# GS_02_Core.net
KiCad netlist of a schematic drawn in Altium Designer
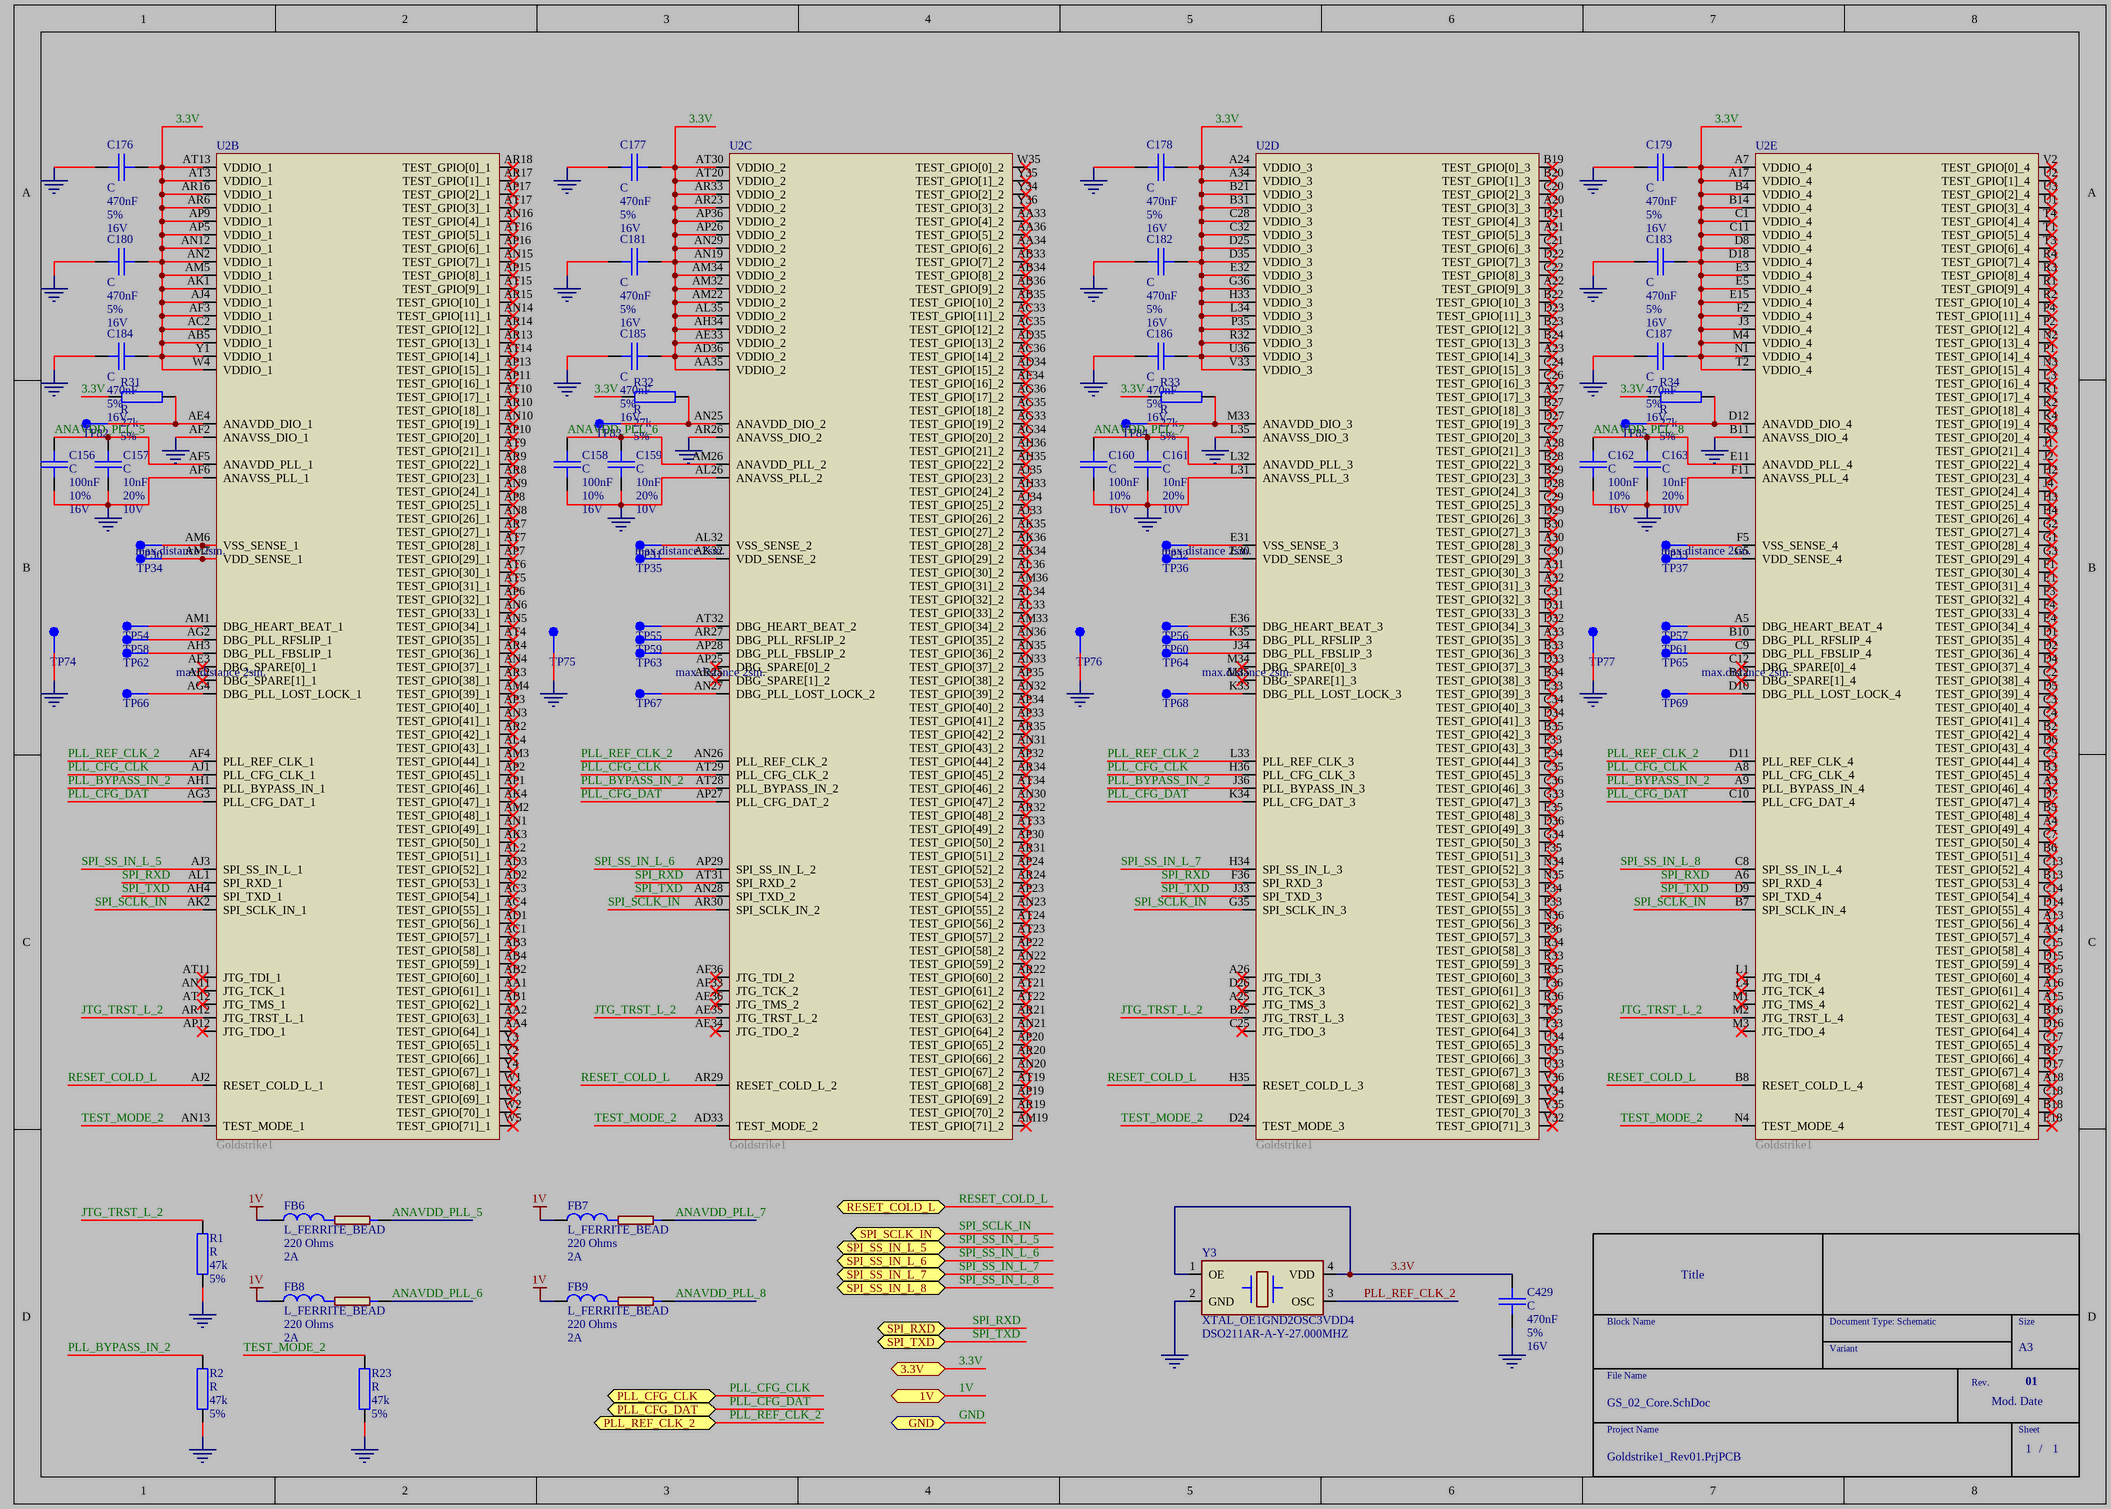
[diagram p0: GS_02_Core.SchDoc]

(export (version "E")
  (design (tool "Eeschema 10.0.6"))
  (components
    (comp (ref "C156")
      (value "C")
      (footprint "SMD_0603_CAPC1608X95N")
      (fields
        (field (name "DB_PART_NUMBER") "CAP000047357")
        (field (name "DB_VALUE") "100nF")
        (field (name "DB_TOLERANCE") "10%")
        (field (name "DB_VOLTAGE") "16V")
        (field (name "DB_MANUFACTURER_PART") "YAGEO      223878615649")
        (field (name "DB_APPROVED_BY") "VSN")
      )
      (libsource (lib "Database_Libs1") (part "C"))
    )
    (comp (ref "C157")
      (value "C")
      (footprint "SMD_0603_CAPC1608X95N")
      (fields
        (field (name "DB_PART_NUMBER") "CAP000038821")
        (field (name "DB_VALUE") "10nF")
        (field (name "DB_TOLERANCE") "20%")
        (field (name "DB_VOLTAGE") "10V")
        (field (name "DB_MANUFACTURER_PART") "KEMET    C0603C103M8GAC")
      )
      (libsource (lib "Database_Libs1") (part "C"))
    )
    (comp (ref "C158")
      (value "C")
      (footprint "SMD_0603_CAPC1608X95N")
      (fields
        (field (name "DB_PART_NUMBER") "CAP000047357")
        (field (name "DB_VALUE") "100nF")
        (field (name "DB_TOLERANCE") "10%")
        (field (name "DB_VOLTAGE") "16V")
        (field (name "DB_MANUFACTURER_PART") "YAGEO      223878615649")
        (field (name "DB_APPROVED_BY") "VSN")
      )
      (libsource (lib "Database_Libs1") (part "C"))
    )
    (comp (ref "C159")
      (value "C")
      (footprint "SMD_0603_CAPC1608X95N")
      (fields
        (field (name "DB_PART_NUMBER") "CAP000038821")
        (field (name "DB_VALUE") "10nF")
        (field (name "DB_TOLERANCE") "20%")
        (field (name "DB_VOLTAGE") "10V")
        (field (name "DB_MANUFACTURER_PART") "KEMET    C0603C103M8GAC")
      )
      (libsource (lib "Database_Libs1") (part "C"))
    )
    (comp (ref "C160")
      (value "C")
      (footprint "SMD_0603_CAPC1608X95N")
      (fields
        (field (name "DB_PART_NUMBER") "CAP000047357")
        (field (name "DB_VALUE") "100nF")
        (field (name "DB_TOLERANCE") "10%")
        (field (name "DB_VOLTAGE") "16V")
        (field (name "DB_MANUFACTURER_PART") "YAGEO      223878615649")
        (field (name "DB_APPROVED_BY") "VSN")
      )
      (libsource (lib "Database_Libs1") (part "C"))
    )
    (comp (ref "C161")
      (value "C")
      (footprint "SMD_0603_CAPC1608X95N")
      (fields
        (field (name "DB_PART_NUMBER") "CAP000038821")
        (field (name "DB_VALUE") "10nF")
        (field (name "DB_TOLERANCE") "20%")
        (field (name "DB_VOLTAGE") "10V")
        (field (name "DB_MANUFACTURER_PART") "KEMET    C0603C103M8GAC")
      )
      (libsource (lib "Database_Libs1") (part "C"))
    )
    (comp (ref "C162")
      (value "C")
      (footprint "SMD_0603_CAPC1608X95N")
      (fields
        (field (name "DB_PART_NUMBER") "CAP000047357")
        (field (name "DB_VALUE") "100nF")
        (field (name "DB_TOLERANCE") "10%")
        (field (name "DB_VOLTAGE") "16V")
        (field (name "DB_MANUFACTURER_PART") "YAGEO      223878615649")
        (field (name "DB_APPROVED_BY") "VSN")
      )
      (libsource (lib "Database_Libs1") (part "C"))
    )
    (comp (ref "C163")
      (value "C")
      (footprint "SMD_0603_CAPC1608X95N")
      (fields
        (field (name "DB_PART_NUMBER") "CAP000038821")
        (field (name "DB_VALUE") "10nF")
        (field (name "DB_TOLERANCE") "20%")
        (field (name "DB_VOLTAGE") "10V")
        (field (name "DB_MANUFACTURER_PART") "KEMET    C0603C103M8GAC")
      )
      (libsource (lib "Database_Libs1") (part "C"))
    )
    (comp (ref "C176")
      (value "C")
      (footprint "SMD_0603_CAPC1608X95N")
      (fields
        (field (name "DB_PART_NUMBER") "CAP000028169")
        (field (name "DB_VALUE") "470nF")
        (field (name "DB_TOLERANCE") "5%")
        (field (name "DB_VOLTAGE") "16V")
        (field (name "DB_MANUFACTURER_PART") "KEMET    C0603C474J4RAC")
      )
      (libsource (lib "Database_Libs1") (part "C"))
    )
    (comp (ref "C177")
      (value "C")
      (footprint "SMD_0603_CAPC1608X95N")
      (fields
        (field (name "DB_PART_NUMBER") "CAP000028169")
        (field (name "DB_VALUE") "470nF")
        (field (name "DB_TOLERANCE") "5%")
        (field (name "DB_VOLTAGE") "16V")
        (field (name "DB_MANUFACTURER_PART") "KEMET    C0603C474J4RAC")
      )
      (libsource (lib "Database_Libs1") (part "C"))
    )
    (comp (ref "C178")
      (value "C")
      (footprint "SMD_0603_CAPC1608X95N")
      (fields
        (field (name "DB_PART_NUMBER") "CAP000028169")
        (field (name "DB_VALUE") "470nF")
        (field (name "DB_TOLERANCE") "5%")
        (field (name "DB_VOLTAGE") "16V")
        (field (name "DB_MANUFACTURER_PART") "KEMET    C0603C474J4RAC")
      )
      (libsource (lib "Database_Libs1") (part "C"))
    )
    (comp (ref "C179")
      (value "C")
      (footprint "SMD_0603_CAPC1608X95N")
      (fields
        (field (name "DB_PART_NUMBER") "CAP000028169")
        (field (name "DB_VALUE") "470nF")
        (field (name "DB_TOLERANCE") "5%")
        (field (name "DB_VOLTAGE") "16V")
        (field (name "DB_MANUFACTURER_PART") "KEMET    C0603C474J4RAC")
      )
      (libsource (lib "Database_Libs1") (part "C"))
    )
    (comp (ref "C180")
      (value "C")
      (footprint "SMD_0603_CAPC1608X95N")
      (fields
        (field (name "DB_PART_NUMBER") "CAP000028169")
        (field (name "DB_VALUE") "470nF")
        (field (name "DB_TOLERANCE") "5%")
        (field (name "DB_VOLTAGE") "16V")
        (field (name "DB_MANUFACTURER_PART") "KEMET    C0603C474J4RAC")
      )
      (libsource (lib "Database_Libs1") (part "C"))
    )
    (comp (ref "C181")
      (value "C")
      (footprint "SMD_0603_CAPC1608X95N")
      (fields
        (field (name "DB_PART_NUMBER") "CAP000028169")
        (field (name "DB_VALUE") "470nF")
        (field (name "DB_TOLERANCE") "5%")
        (field (name "DB_VOLTAGE") "16V")
        (field (name "DB_MANUFACTURER_PART") "KEMET    C0603C474J4RAC")
      )
      (libsource (lib "Database_Libs1") (part "C"))
    )
    (comp (ref "C182")
      (value "C")
      (footprint "SMD_0603_CAPC1608X95N")
      (fields
        (field (name "DB_PART_NUMBER") "CAP000028169")
        (field (name "DB_VALUE") "470nF")
        (field (name "DB_TOLERANCE") "5%")
        (field (name "DB_VOLTAGE") "16V")
        (field (name "DB_MANUFACTURER_PART") "KEMET    C0603C474J4RAC")
      )
      (libsource (lib "Database_Libs1") (part "C"))
    )
    (comp (ref "C183")
      (value "C")
      (footprint "SMD_0603_CAPC1608X95N")
      (fields
        (field (name "DB_PART_NUMBER") "CAP000028169")
        (field (name "DB_VALUE") "470nF")
        (field (name "DB_TOLERANCE") "5%")
        (field (name "DB_VOLTAGE") "16V")
        (field (name "DB_MANUFACTURER_PART") "KEMET    C0603C474J4RAC")
      )
      (libsource (lib "Database_Libs1") (part "C"))
    )
    (comp (ref "C184")
      (value "C")
      (footprint "SMD_0603_CAPC1608X95N")
      (fields
        (field (name "DB_PART_NUMBER") "CAP000028169")
        (field (name "DB_VALUE") "470nF")
        (field (name "DB_TOLERANCE") "5%")
        (field (name "DB_VOLTAGE") "16V")
        (field (name "DB_MANUFACTURER_PART") "KEMET    C0603C474J4RAC")
      )
      (libsource (lib "Database_Libs1") (part "C"))
    )
    (comp (ref "C185")
      (value "C")
      (footprint "SMD_0603_CAPC1608X95N")
      (fields
        (field (name "DB_PART_NUMBER") "CAP000028169")
        (field (name "DB_VALUE") "470nF")
        (field (name "DB_TOLERANCE") "5%")
        (field (name "DB_VOLTAGE") "16V")
        (field (name "DB_MANUFACTURER_PART") "KEMET    C0603C474J4RAC")
      )
      (libsource (lib "Database_Libs1") (part "C"))
    )
    (comp (ref "C186")
      (value "C")
      (footprint "SMD_0603_CAPC1608X95N")
      (fields
        (field (name "DB_PART_NUMBER") "CAP000028169")
        (field (name "DB_VALUE") "470nF")
        (field (name "DB_TOLERANCE") "5%")
        (field (name "DB_VOLTAGE") "16V")
        (field (name "DB_MANUFACTURER_PART") "KEMET    C0603C474J4RAC")
      )
      (libsource (lib "Database_Libs1") (part "C"))
    )
    (comp (ref "C187")
      (value "C")
      (footprint "SMD_0603_CAPC1608X95N")
      (fields
        (field (name "DB_PART_NUMBER") "CAP000028169")
        (field (name "DB_VALUE") "470nF")
        (field (name "DB_TOLERANCE") "5%")
        (field (name "DB_VOLTAGE") "16V")
        (field (name "DB_MANUFACTURER_PART") "KEMET    C0603C474J4RAC")
      )
      (libsource (lib "Database_Libs1") (part "C"))
    )
    (comp (ref "C429")
      (value "C")
      (footprint "SMD_0603_CAPC1608X95N")
      (fields
        (field (name "DB_PART_NUMBER") "CAP000028169")
        (field (name "DB_VALUE") "470nF")
        (field (name "DB_TOLERANCE") "5%")
        (field (name "DB_VOLTAGE") "16V")
        (field (name "DB_MANUFACTURER_PART") "KEMET    C0603C474J4RAC")
      )
      (libsource (lib "Database_Libs1") (part "C"))
    )
    (comp (ref "FB6")
      (value "L_FERRITE_BEAD")
      (footprint "SMD_0805_INDC2012X105N")
      (fields
        (field (name "DB_PART_NUMBER") "IND000000029")
        (field (name "DB_VALUE") "220 Ohms")
        (field (name "DB_CURRENT") "2A")
        (field (name "DB_MANUFACTURER_PART") "MURATA       BLM21PG221SN1D")
        (field (name "DB_APPROVED_BY") "VSN")
      )
      (libsource (lib "Database_Libs1") (part "L_FERRITE_BEAD"))
    )
    (comp (ref "FB7")
      (value "L_FERRITE_BEAD")
      (footprint "SMD_0805_INDC2012X105N")
      (fields
        (field (name "DB_PART_NUMBER") "IND000000029")
        (field (name "DB_VALUE") "220 Ohms")
        (field (name "DB_CURRENT") "2A")
        (field (name "DB_MANUFACTURER_PART") "MURATA       BLM21PG221SN1D")
        (field (name "DB_APPROVED_BY") "VSN")
      )
      (libsource (lib "Database_Libs1") (part "L_FERRITE_BEAD"))
    )
    (comp (ref "FB8")
      (value "L_FERRITE_BEAD")
      (footprint "SMD_0805_INDC2012X105N")
      (fields
        (field (name "DB_PART_NUMBER") "IND000000029")
        (field (name "DB_VALUE") "220 Ohms")
        (field (name "DB_CURRENT") "2A")
        (field (name "DB_MANUFACTURER_PART") "MURATA       BLM21PG221SN1D")
        (field (name "DB_APPROVED_BY") "VSN")
      )
      (libsource (lib "Database_Libs1") (part "L_FERRITE_BEAD"))
    )
    (comp (ref "FB9")
      (value "L_FERRITE_BEAD")
      (footprint "SMD_0805_INDC2012X105N")
      (fields
        (field (name "DB_PART_NUMBER") "IND000000029")
        (field (name "DB_VALUE") "220 Ohms")
        (field (name "DB_CURRENT") "2A")
        (field (name "DB_MANUFACTURER_PART") "MURATA       BLM21PG221SN1D")
        (field (name "DB_APPROVED_BY") "VSN")
      )
      (libsource (lib "Database_Libs1") (part "L_FERRITE_BEAD"))
    )
    (comp (ref "R1")
      (value "R")
      (footprint "SMD_0603_RESC1608X55N")
      (fields
        (field (name "DB_PART_NUMBER") "RES000006462")
        (field (name "DB_VALUE") "47k")
        (field (name "DB_TOLERANCE") "5%")
        (field (name "DB_MANUFACTURER_PART") "YAGEO    RC0603JR-0747K")
      )
      (libsource (lib "Database_Libs1") (part "R"))
    )
    (comp (ref "R2")
      (value "R")
      (footprint "SMD_0603_RESC1608X55N")
      (fields
        (field (name "DB_PART_NUMBER") "RES000006462")
        (field (name "DB_VALUE") "47k")
        (field (name "DB_TOLERANCE") "5%")
        (field (name "DB_MANUFACTURER_PART") "YAGEO    RC0603JR-0747K")
      )
      (libsource (lib "Database_Libs1") (part "R"))
    )
    (comp (ref "R23")
      (value "R")
      (footprint "SMD_0603_RESC1608X55N")
      (fields
        (field (name "DB_PART_NUMBER") "RES000006462")
        (field (name "DB_VALUE") "47k")
        (field (name "DB_TOLERANCE") "5%")
        (field (name "DB_MANUFACTURER_PART") "YAGEO    RC0603JR-0747K")
      )
      (libsource (lib "Database_Libs1") (part "R"))
    )
    (comp (ref "R31")
      (value "R")
      (footprint "SMD_0603_RESC1608X55N")
      (fields
        (field (name "DB_PART_NUMBER") "RES000006456")
        (field (name "DB_VALUE") "27k")
        (field (name "DB_TOLERANCE") "5%")
        (field (name "DB_MANUFACTURER_PART") "YAGEO    RC0603JR-0727K")
      )
      (libsource (lib "Database_Libs1") (part "R"))
    )
    (comp (ref "R32")
      (value "R")
      (footprint "SMD_0603_RESC1608X55N")
      (fields
        (field (name "DB_PART_NUMBER") "RES000006456")
        (field (name "DB_VALUE") "27k")
        (field (name "DB_TOLERANCE") "5%")
        (field (name "DB_MANUFACTURER_PART") "YAGEO    RC0603JR-0727K")
      )
      (libsource (lib "Database_Libs1") (part "R"))
    )
    (comp (ref "R33")
      (value "R")
      (footprint "SMD_0603_RESC1608X55N")
      (fields
        (field (name "DB_PART_NUMBER") "RES000006456")
        (field (name "DB_VALUE") "27k")
        (field (name "DB_TOLERANCE") "5%")
        (field (name "DB_MANUFACTURER_PART") "YAGEO    RC0603JR-0727K")
      )
      (libsource (lib "Database_Libs1") (part "R"))
    )
    (comp (ref "R34")
      (value "R")
      (footprint "SMD_0603_RESC1608X55N")
      (fields
        (field (name "DB_PART_NUMBER") "RES000006456")
        (field (name "DB_VALUE") "27k")
        (field (name "DB_TOLERANCE") "5%")
        (field (name "DB_MANUFACTURER_PART") "YAGEO    RC0603JR-0727K")
      )
      (libsource (lib "Database_Libs1") (part "R"))
    )
    (comp (ref "TP30")
      (value "TEST_POINT_1")
      (footprint "SMD_TP_100-254")
      (fields (field (name "DB_PART_NUMBER") "TPO000000001"))
      (libsource (lib "Database_Libs1") (part "TEST_POINT_1"))
    )
    (comp (ref "TP31")
      (value "TEST_POINT_1")
      (footprint "SMD_TP_100-254")
      (fields (field (name "DB_PART_NUMBER") "TPO000000001"))
      (libsource (lib "Database_Libs1") (part "TEST_POINT_1"))
    )
    (comp (ref "TP32")
      (value "TEST_POINT_1")
      (footprint "SMD_TP_100-254")
      (fields (field (name "DB_PART_NUMBER") "TPO000000001"))
      (libsource (lib "Database_Libs1") (part "TEST_POINT_1"))
    )
    (comp (ref "TP33")
      (value "TEST_POINT_1")
      (footprint "SMD_TP_100-254")
      (fields (field (name "DB_PART_NUMBER") "TPO000000001"))
      (libsource (lib "Database_Libs1") (part "TEST_POINT_1"))
    )
    (comp (ref "TP34")
      (value "TEST_POINT_1")
      (footprint "SMD_TP_100-254")
      (fields (field (name "DB_PART_NUMBER") "TPO000000001"))
      (libsource (lib "Database_Libs1") (part "TEST_POINT_1"))
    )
    (comp (ref "TP35")
      (value "TEST_POINT_1")
      (footprint "SMD_TP_100-254")
      (fields (field (name "DB_PART_NUMBER") "TPO000000001"))
      (libsource (lib "Database_Libs1") (part "TEST_POINT_1"))
    )
    (comp (ref "TP36")
      (value "TEST_POINT_1")
      (footprint "SMD_TP_100-254")
      (fields (field (name "DB_PART_NUMBER") "TPO000000001"))
      (libsource (lib "Database_Libs1") (part "TEST_POINT_1"))
    )
    (comp (ref "TP37")
      (value "TEST_POINT_1")
      (footprint "SMD_TP_100-254")
      (fields (field (name "DB_PART_NUMBER") "TPO000000001"))
      (libsource (lib "Database_Libs1") (part "TEST_POINT_1"))
    )
    (comp (ref "TP54")
      (value "TEST_POINT_1")
      (footprint "SMD_TP_100-254")
      (fields (field (name "DB_PART_NUMBER") "TPO000000001"))
      (libsource (lib "Database_Libs1") (part "TEST_POINT_1"))
    )
    (comp (ref "TP55")
      (value "TEST_POINT_1")
      (footprint "SMD_TP_100-254")
      (fields (field (name "DB_PART_NUMBER") "TPO000000001"))
      (libsource (lib "Database_Libs1") (part "TEST_POINT_1"))
    )
    (comp (ref "TP56")
      (value "TEST_POINT_1")
      (footprint "SMD_TP_100-254")
      (fields (field (name "DB_PART_NUMBER") "TPO000000001"))
      (libsource (lib "Database_Libs1") (part "TEST_POINT_1"))
    )
    (comp (ref "TP57")
      (value "TEST_POINT_1")
      (footprint "SMD_TP_100-254")
      (fields (field (name "DB_PART_NUMBER") "TPO000000001"))
      (libsource (lib "Database_Libs1") (part "TEST_POINT_1"))
    )
    (comp (ref "TP58")
      (value "TEST_POINT_1")
      (footprint "SMD_TP_100-254")
      (fields (field (name "DB_PART_NUMBER") "TPO000000001"))
      (libsource (lib "Database_Libs1") (part "TEST_POINT_1"))
    )
    (comp (ref "TP59")
      (value "TEST_POINT_1")
      (footprint "SMD_TP_100-254")
      (fields (field (name "DB_PART_NUMBER") "TPO000000001"))
      (libsource (lib "Database_Libs1") (part "TEST_POINT_1"))
    )
    (comp (ref "TP60")
      (value "TEST_POINT_1")
      (footprint "SMD_TP_100-254")
      (fields (field (name "DB_PART_NUMBER") "TPO000000001"))
      (libsource (lib "Database_Libs1") (part "TEST_POINT_1"))
    )
    (comp (ref "TP61")
      (value "TEST_POINT_1")
      (footprint "SMD_TP_100-254")
      (fields (field (name "DB_PART_NUMBER") "TPO000000001"))
      (libsource (lib "Database_Libs1") (part "TEST_POINT_1"))
    )
    (comp (ref "TP62")
      (value "TEST_POINT_1")
      (footprint "SMD_TP_100-254")
      (fields (field (name "DB_PART_NUMBER") "TPO000000001"))
      (libsource (lib "Database_Libs1") (part "TEST_POINT_1"))
    )
    (comp (ref "TP63")
      (value "TEST_POINT_1")
      (footprint "SMD_TP_100-254")
      (fields (field (name "DB_PART_NUMBER") "TPO000000001"))
      (libsource (lib "Database_Libs1") (part "TEST_POINT_1"))
    )
    (comp (ref "TP64")
      (value "TEST_POINT_1")
      (footprint "SMD_TP_100-254")
      (fields (field (name "DB_PART_NUMBER") "TPO000000001"))
      (libsource (lib "Database_Libs1") (part "TEST_POINT_1"))
    )
    (comp (ref "TP65")
      (value "TEST_POINT_1")
      (footprint "SMD_TP_100-254")
      (fields (field (name "DB_PART_NUMBER") "TPO000000001"))
      (libsource (lib "Database_Libs1") (part "TEST_POINT_1"))
    )
    (comp (ref "TP66")
      (value "TEST_POINT_1")
      (footprint "SMD_TP_100-254")
      (fields (field (name "DB_PART_NUMBER") "TPO000000001"))
      (libsource (lib "Database_Libs1") (part "TEST_POINT_1"))
    )
    (comp (ref "TP67")
      (value "TEST_POINT_1")
      (footprint "SMD_TP_100-254")
      (fields (field (name "DB_PART_NUMBER") "TPO000000001"))
      (libsource (lib "Database_Libs1") (part "TEST_POINT_1"))
    )
    (comp (ref "TP68")
      (value "TEST_POINT_1")
      (footprint "SMD_TP_100-254")
      (fields (field (name "DB_PART_NUMBER") "TPO000000001"))
      (libsource (lib "Database_Libs1") (part "TEST_POINT_1"))
    )
    (comp (ref "TP69")
      (value "TEST_POINT_1")
      (footprint "SMD_TP_100-254")
      (fields (field (name "DB_PART_NUMBER") "TPO000000001"))
      (libsource (lib "Database_Libs1") (part "TEST_POINT_1"))
    )
    (comp (ref "TP74")
      (value "TEST_POINT_1")
      (footprint "SMD_TP_100-254")
      (fields (field (name "DB_PART_NUMBER") "TPO000000001"))
      (libsource (lib "Database_Libs1") (part "TEST_POINT_1"))
    )
    (comp (ref "TP75")
      (value "TEST_POINT_1")
      (footprint "SMD_TP_100-254")
      (fields (field (name "DB_PART_NUMBER") "TPO000000001"))
      (libsource (lib "Database_Libs1") (part "TEST_POINT_1"))
    )
    (comp (ref "TP76")
      (value "TEST_POINT_1")
      (footprint "SMD_TP_100-254")
      (fields (field (name "DB_PART_NUMBER") "TPO000000001"))
      (libsource (lib "Database_Libs1") (part "TEST_POINT_1"))
    )
    (comp (ref "TP77")
      (value "TEST_POINT_1")
      (footprint "SMD_TP_100-254")
      (fields (field (name "DB_PART_NUMBER") "TPO000000001"))
      (libsource (lib "Database_Libs1") (part "TEST_POINT_1"))
    )
    (comp (ref "TP82")
      (value "TEST_POINT_1")
      (footprint "SMD_TP_100-254")
      (fields (field (name "DB_PART_NUMBER") "TPO000000001"))
      (libsource (lib "Database_Libs1") (part "TEST_POINT_1"))
    )
    (comp (ref "TP83")
      (value "TEST_POINT_1")
      (footprint "SMD_TP_100-254")
      (fields (field (name "DB_PART_NUMBER") "TPO000000001"))
      (libsource (lib "Database_Libs1") (part "TEST_POINT_1"))
    )
    (comp (ref "TP84")
      (value "TEST_POINT_1")
      (footprint "SMD_TP_100-254")
      (fields (field (name "DB_PART_NUMBER") "TPO000000001"))
      (libsource (lib "Database_Libs1") (part "TEST_POINT_1"))
    )
    (comp (ref "TP85")
      (value "TEST_POINT_1")
      (footprint "SMD_TP_100-254")
      (fields (field (name "DB_PART_NUMBER") "TPO000000001"))
      (libsource (lib "Database_Libs1") (part "TEST_POINT_1"))
    )
    (comp (ref "U2")
      (value "Goldstrike1")
      (footprint "SMD_BGA1296C100P36X36")
      (libsource (lib "Schlib1") (part "Goldstrike1"))
    )
    (comp (ref "Y3")
      (value "XTAL_OE1GND2OSC3VDD4")
      (footprint "SMD_OSCCC160X200X80-4N")
      (fields
        (field (name "DB_PART_NUMBER") "OSC000000015")
        (field (name "DB_VALUE") "DSO211AR-A-Y-27.000MHZ")
        (field (name "DB_MANUFACTURER_PART") "KDS DAISHINKU      DSO211AR-A-Y-27.000MHZ")
        (field (name "DB_APPROVED_BY") "VSN")
      )
      (libsource (lib "Database_Libs1") (part "XTAL_OE1GND2OSC3VDD4"))
    )
  )
  (nets
    (net (code "1") (name "/3.3V") (class "Default")
      (node (ref "C176") (pin "2") (pinfunction "2_2") (pintype "passive"))
      (node (ref "C177") (pin "2") (pinfunction "2_2") (pintype "passive"))
      (node (ref "C178") (pin "2") (pinfunction "2_2") (pintype "passive"))
      (node (ref "C179") (pin "2") (pinfunction "2_2") (pintype "passive"))
      (node (ref "C180") (pin "2") (pinfunction "2_2") (pintype "passive"))
      (node (ref "C181") (pin "2") (pinfunction "2_2") (pintype "passive"))
      (node (ref "C182") (pin "2") (pinfunction "2_2") (pintype "passive"))
      (node (ref "C183") (pin "2") (pinfunction "2_2") (pintype "passive"))
      (node (ref "C184") (pin "2") (pinfunction "2_2") (pintype "passive"))
      (node (ref "C185") (pin "2") (pinfunction "2_2") (pintype "passive"))
      (node (ref "C186") (pin "2") (pinfunction "2_2") (pintype "passive"))
      (node (ref "C187") (pin "2") (pinfunction "2_2") (pintype "passive"))
      (node (ref "C429") (pin "2") (pinfunction "2_2") (pintype "passive"))
      (node (ref "R31") (pin "1") (pinfunction "1_1") (pintype "passive"))
      (node (ref "R32") (pin "1") (pinfunction "1_1") (pintype "passive"))
      (node (ref "R33") (pin "1") (pinfunction "1_1") (pintype "passive"))
      (node (ref "R34") (pin "1") (pinfunction "1_1") (pintype "passive"))
      (node (ref "U2") (pin "A17") (pinfunction "VDDIO_4_A17") (pintype "passive"))
      (node (ref "U2") (pin "A24") (pinfunction "VDDIO_3_A24") (pintype "passive"))
      (node (ref "U2") (pin "A34") (pinfunction "VDDIO_3_A34") (pintype "passive"))
      (node (ref "U2") (pin "A7") (pinfunction "VDDIO_4_A7") (pintype "passive"))
      (node (ref "U2") (pin "AA35") (pinfunction "VDDIO_2_AA35") (pintype "passive"))
      (node (ref "U2") (pin "AB5") (pinfunction "VDDIO_1_AB5") (pintype "passive"))
      (node (ref "U2") (pin "AC2") (pinfunction "VDDIO_1_AC2") (pintype "passive"))
      (node (ref "U2") (pin "AD36") (pinfunction "VDDIO_2_AD36") (pintype "passive"))
      (node (ref "U2") (pin "AE33") (pinfunction "VDDIO_2_AE33") (pintype "passive"))
      (node (ref "U2") (pin "AF3") (pinfunction "VDDIO_1_AF3") (pintype "passive"))
      (node (ref "U2") (pin "AH34") (pinfunction "VDDIO_2_AH34") (pintype "passive"))
      (node (ref "U2") (pin "AJ4") (pinfunction "VDDIO_1_AJ4") (pintype "passive"))
      (node (ref "U2") (pin "AK1") (pinfunction "VDDIO_1_AK1") (pintype "passive"))
      (node (ref "U2") (pin "AL35") (pinfunction "VDDIO_2_AL35") (pintype "passive"))
      (node (ref "U2") (pin "AM22") (pinfunction "VDDIO_2_AM22") (pintype "passive"))
      (node (ref "U2") (pin "AM32") (pinfunction "VDDIO_2_AM32") (pintype "passive"))
      (node (ref "U2") (pin "AM34") (pinfunction "VDDIO_2_AM34") (pintype "passive"))
      (node (ref "U2") (pin "AM5") (pinfunction "VDDIO_1_AM5") (pintype "passive"))
      (node (ref "U2") (pin "AN12") (pinfunction "VDDIO_1_AN12") (pintype "passive"))
      (node (ref "U2") (pin "AN19") (pinfunction "VDDIO_2_AN19") (pintype "passive"))
      (node (ref "U2") (pin "AN2") (pinfunction "VDDIO_1_AN2") (pintype "passive"))
      (node (ref "U2") (pin "AN29") (pinfunction "VDDIO_2_AN29") (pintype "passive"))
      (node (ref "U2") (pin "AP26") (pinfunction "VDDIO_2_AP26") (pintype "passive"))
      (node (ref "U2") (pin "AP36") (pinfunction "VDDIO_2_AP36") (pintype "passive"))
      (node (ref "U2") (pin "AP5") (pinfunction "VDDIO_1_AP5") (pintype "passive"))
      (node (ref "U2") (pin "AP9") (pinfunction "VDDIO_1_AP9") (pintype "passive"))
      (node (ref "U2") (pin "AR16") (pinfunction "VDDIO_1_AR16") (pintype "passive"))
      (node (ref "U2") (pin "AR23") (pinfunction "VDDIO_2_AR23") (pintype "passive"))
      (node (ref "U2") (pin "AR33") (pinfunction "VDDIO_2_AR33") (pintype "passive"))
      (node (ref "U2") (pin "AR6") (pinfunction "VDDIO_1_AR6") (pintype "passive"))
      (node (ref "U2") (pin "AT13") (pinfunction "VDDIO_1_AT13") (pintype "passive"))
      (node (ref "U2") (pin "AT20") (pinfunction "VDDIO_2_AT20") (pintype "passive"))
      (node (ref "U2") (pin "AT3") (pinfunction "VDDIO_1_AT3") (pintype "passive"))
      (node (ref "U2") (pin "AT30") (pinfunction "VDDIO_2_AT30") (pintype "passive"))
      (node (ref "U2") (pin "B14") (pinfunction "VDDIO_4_B14") (pintype "passive"))
      (node (ref "U2") (pin "B21") (pinfunction "VDDIO_3_B21") (pintype "passive"))
      (node (ref "U2") (pin "B31") (pinfunction "VDDIO_3_B31") (pintype "passive"))
      (node (ref "U2") (pin "B4") (pinfunction "VDDIO_4_B4") (pintype "passive"))
      (node (ref "U2") (pin "C1") (pinfunction "VDDIO_4_C1") (pintype "passive"))
      (node (ref "U2") (pin "C11") (pinfunction "VDDIO_4_C11") (pintype "passive"))
      (node (ref "U2") (pin "C28") (pinfunction "VDDIO_3_C28") (pintype "passive"))
      (node (ref "U2") (pin "C32") (pinfunction "VDDIO_3_C32") (pintype "passive"))
      (node (ref "U2") (pin "D18") (pinfunction "VDDIO_4_D18") (pintype "passive"))
      (node (ref "U2") (pin "D25") (pinfunction "VDDIO_3_D25") (pintype "passive"))
      (node (ref "U2") (pin "D35") (pinfunction "VDDIO_3_D35") (pintype "passive"))
      (node (ref "U2") (pin "D8") (pinfunction "VDDIO_4_D8") (pintype "passive"))
      (node (ref "U2") (pin "E15") (pinfunction "VDDIO_4_E15") (pintype "passive"))
      (node (ref "U2") (pin "E3") (pinfunction "VDDIO_4_E3") (pintype "passive"))
      (node (ref "U2") (pin "E32") (pinfunction "VDDIO_3_E32") (pintype "passive"))
      (node (ref "U2") (pin "E5") (pinfunction "VDDIO_4_E5") (pintype "passive"))
      (node (ref "U2") (pin "F2") (pinfunction "VDDIO_4_F2") (pintype "passive"))
      (node (ref "U2") (pin "G36") (pinfunction "VDDIO_3_G36") (pintype "passive"))
      (node (ref "U2") (pin "H33") (pinfunction "VDDIO_3_H33") (pintype "passive"))
      (node (ref "U2") (pin "J3") (pinfunction "VDDIO_4_J3") (pintype "passive"))
      (node (ref "U2") (pin "L34") (pinfunction "VDDIO_3_L34") (pintype "passive"))
      (node (ref "U2") (pin "M4") (pinfunction "VDDIO_4_M4") (pintype "passive"))
      (node (ref "U2") (pin "N1") (pinfunction "VDDIO_4_N1") (pintype "passive"))
      (node (ref "U2") (pin "P35") (pinfunction "VDDIO_3_P35") (pintype "passive"))
      (node (ref "U2") (pin "R32") (pinfunction "VDDIO_3_R32") (pintype "passive"))
      (node (ref "U2") (pin "T2") (pinfunction "VDDIO_4_T2") (pintype "passive"))
      (node (ref "U2") (pin "U36") (pinfunction "VDDIO_3_U36") (pintype "passive"))
      (node (ref "U2") (pin "V33") (pinfunction "VDDIO_3_V33") (pintype "passive"))
      (node (ref "U2") (pin "W4") (pinfunction "VDDIO_1_W4") (pintype "passive"))
      (node (ref "U2") (pin "Y1") (pinfunction "VDDIO_1_Y1") (pintype "passive"))
      (node (ref "Y3") (pin "1") (pinfunction "OE_1") (pintype "passive"))
      (node (ref "Y3") (pin "4") (pinfunction "VDD_4") (pintype "passive"))
    )
    (net (code "2") (name "/ANAVDD_PLL_5") (class "Default")
      (node (ref "C156") (pin "1") (pinfunction "1_1") (pintype "passive"))
      (node (ref "C157") (pin "1") (pinfunction "1_1") (pintype "passive"))
      (node (ref "FB6") (pin "2") (pinfunction "2_2") (pintype "passive"))
      (node (ref "U2") (pin "AF5") (pinfunction "ANAVDD_PLL_1_AF5") (pintype "passive"))
    )
    (net (code "3") (name "/ANAVDD_PLL_6") (class "Default")
      (node (ref "C158") (pin "1") (pinfunction "1_1") (pintype "passive"))
      (node (ref "C159") (pin "1") (pinfunction "1_1") (pintype "passive"))
      (node (ref "FB8") (pin "2") (pinfunction "2_2") (pintype "passive"))
      (node (ref "U2") (pin "AM26") (pinfunction "ANAVDD_PLL_2_AM26") (pintype "passive"))
    )
    (net (code "4") (name "/ANAVDD_PLL_7") (class "Default")
      (node (ref "C160") (pin "1") (pinfunction "1_1") (pintype "passive"))
      (node (ref "C161") (pin "1") (pinfunction "1_1") (pintype "passive"))
      (node (ref "FB7") (pin "2") (pinfunction "2_2") (pintype "passive"))
      (node (ref "U2") (pin "L32") (pinfunction "ANAVDD_PLL_3_L32") (pintype "passive"))
    )
    (net (code "5") (name "/ANAVDD_PLL_8") (class "Default")
      (node (ref "C162") (pin "1") (pinfunction "1_1") (pintype "passive"))
      (node (ref "C163") (pin "1") (pinfunction "1_1") (pintype "passive"))
      (node (ref "FB9") (pin "2") (pinfunction "2_2") (pintype "passive"))
      (node (ref "U2") (pin "E11") (pinfunction "ANAVDD_PLL_4_E11") (pintype "passive"))
    )
    (net (code "6") (name "/JTG_TRST_L_2") (class "Default")
      (node (ref "R1") (pin "1") (pinfunction "1_1") (pintype "passive"))
      (node (ref "U2") (pin "AE35") (pinfunction "JTG_TRST_L_2_AE35") (pintype "passive"))
      (node (ref "U2") (pin "AR12") (pinfunction "JTG_TRST_L_1_AR12") (pintype "passive"))
      (node (ref "U2") (pin "B25") (pinfunction "JTG_TRST_L_3_B25") (pintype "passive"))
      (node (ref "U2") (pin "M2") (pinfunction "JTG_TRST_L_4_M2") (pintype "passive"))
    )
    (net (code "7") (name "/PLL_BYPASS_IN_2") (class "Default")
      (node (ref "R2") (pin "1") (pinfunction "1_1") (pintype "passive"))
      (node (ref "U2") (pin "A9") (pinfunction "PLL_BYPASS_IN_4_A9") (pintype "passive"))
      (node (ref "U2") (pin "AH1") (pinfunction "PLL_BYPASS_IN_1_AH1") (pintype "passive"))
      (node (ref "U2") (pin "AT28") (pinfunction "PLL_BYPASS_IN_2_AT28") (pintype "passive"))
      (node (ref "U2") (pin "J36") (pinfunction "PLL_BYPASS_IN_3_J36") (pintype "passive"))
    )
    (net (code "8") (name "/PLL_CFG_CLK") (class "Default")
      (node (ref "U2") (pin "A8") (pinfunction "PLL_CFG_CLK_4_A8") (pintype "passive"))
      (node (ref "U2") (pin "AJ1") (pinfunction "PLL_CFG_CLK_1_AJ1") (pintype "passive"))
      (node (ref "U2") (pin "AT29") (pinfunction "PLL_CFG_CLK_2_AT29") (pintype "passive"))
      (node (ref "U2") (pin "H36") (pinfunction "PLL_CFG_CLK_3_H36") (pintype "passive"))
    )
    (net (code "9") (name "/PLL_CFG_DAT") (class "Default")
      (node (ref "U2") (pin "AG3") (pinfunction "PLL_CFG_DAT_1_AG3") (pintype "passive"))
      (node (ref "U2") (pin "AP27") (pinfunction "PLL_CFG_DAT_2_AP27") (pintype "passive"))
      (node (ref "U2") (pin "C10") (pinfunction "PLL_CFG_DAT_4_C10") (pintype "passive"))
      (node (ref "U2") (pin "K34") (pinfunction "PLL_CFG_DAT_3_K34") (pintype "passive"))
    )
    (net (code "10") (name "/PLL_REF_CLK_2") (class "Default")
      (node (ref "U2") (pin "AF4") (pinfunction "PLL_REF_CLK_1_AF4") (pintype "passive"))
      (node (ref "U2") (pin "AN26") (pinfunction "PLL_REF_CLK_2_AN26") (pintype "passive"))
      (node (ref "U2") (pin "D11") (pinfunction "PLL_REF_CLK_4_D11") (pintype "passive"))
      (node (ref "U2") (pin "L33") (pinfunction "PLL_REF_CLK_3_L33") (pintype "passive"))
      (node (ref "Y3") (pin "3") (pinfunction "OSC_3") (pintype "passive"))
    )
    (net (code "11") (name "/RESET_COLD_L") (class "Default")
      (node (ref "U2") (pin "AJ2") (pinfunction "RESET_COLD_L_1_AJ2") (pintype "passive"))
      (node (ref "U2") (pin "AR29") (pinfunction "RESET_COLD_L_2_AR29") (pintype "passive"))
      (node (ref "U2") (pin "B8") (pinfunction "RESET_COLD_L_4_B8") (pintype "passive"))
      (node (ref "U2") (pin "H35") (pinfunction "RESET_COLD_L_3_H35") (pintype "passive"))
    )
    (net (code "12") (name "/SPI_RXD") (class "Default")
      (node (ref "U2") (pin "A6") (pinfunction "SPI_RXD_4_A6") (pintype "passive"))
      (node (ref "U2") (pin "AL1") (pinfunction "SPI_RXD_1_AL1") (pintype "passive"))
      (node (ref "U2") (pin "AT31") (pinfunction "SPI_RXD_2_AT31") (pintype "passive"))
      (node (ref "U2") (pin "F36") (pinfunction "SPI_RXD_3_F36") (pintype "passive"))
    )
    (net (code "13") (name "/SPI_SCLK_IN") (class "Default")
      (node (ref "U2") (pin "AK2") (pinfunction "SPI_SCLK_IN_1_AK2") (pintype "passive"))
      (node (ref "U2") (pin "AR30") (pinfunction "SPI_SCLK_IN_2_AR30") (pintype "passive"))
      (node (ref "U2") (pin "B7") (pinfunction "SPI_SCLK_IN_4_B7") (pintype "passive"))
      (node (ref "U2") (pin "G35") (pinfunction "SPI_SCLK_IN_3_G35") (pintype "passive"))
    )
    (net (code "14") (name "/SPI_SS_IN_L_5") (class "Default")
      (node (ref "U2") (pin "AJ3") (pinfunction "SPI_SS_IN_L_1_AJ3") (pintype "passive"))
    )
    (net (code "15") (name "/SPI_SS_IN_L_6") (class "Default")
      (node (ref "U2") (pin "AP29") (pinfunction "SPI_SS_IN_L_2_AP29") (pintype "passive"))
    )
    (net (code "16") (name "/SPI_SS_IN_L_7") (class "Default")
      (node (ref "U2") (pin "H34") (pinfunction "SPI_SS_IN_L_3_H34") (pintype "passive"))
    )
    (net (code "17") (name "/SPI_SS_IN_L_8") (class "Default")
      (node (ref "U2") (pin "C8") (pinfunction "SPI_SS_IN_L_4_C8") (pintype "passive"))
    )
    (net (code "18") (name "/SPI_TXD") (class "Default")
      (node (ref "U2") (pin "AH4") (pinfunction "SPI_TXD_1_AH4") (pintype "passive"))
      (node (ref "U2") (pin "AN28") (pinfunction "SPI_TXD_2_AN28") (pintype "passive"))
      (node (ref "U2") (pin "D9") (pinfunction "SPI_TXD_4_D9") (pintype "passive"))
      (node (ref "U2") (pin "J33") (pinfunction "SPI_TXD_3_J33") (pintype "passive"))
    )
    (net (code "19") (name "/TEST_MODE_2") (class "Default")
      (node (ref "R23") (pin "1") (pinfunction "1_1") (pintype "passive"))
      (node (ref "U2") (pin "AD33") (pinfunction "TEST_MODE_2_AD33") (pintype "passive"))
      (node (ref "U2") (pin "AN13") (pinfunction "TEST_MODE_1_AN13") (pintype "passive"))
      (node (ref "U2") (pin "D24") (pinfunction "TEST_MODE_3_D24") (pintype "passive"))
      (node (ref "U2") (pin "N4") (pinfunction "TEST_MODE_4_N4") (pintype "passive"))
    )
    (net (code "20") (name "1V") (class "Default")
      (node (ref "FB6") (pin "1") (pinfunction "1_1") (pintype "passive"))
      (node (ref "FB7") (pin "1") (pinfunction "1_1") (pintype "passive"))
      (node (ref "FB8") (pin "1") (pinfunction "1_1") (pintype "passive"))
      (node (ref "FB9") (pin "1") (pinfunction "1_1") (pintype "passive"))
    )
    (net (code "21") (name "GND") (class "Default")
      (node (ref "C156") (pin "2") (pinfunction "2_2") (pintype "passive"))
      (node (ref "C157") (pin "2") (pinfunction "2_2") (pintype "passive"))
      (node (ref "C158") (pin "2") (pinfunction "2_2") (pintype "passive"))
      (node (ref "C159") (pin "2") (pinfunction "2_2") (pintype "passive"))
      (node (ref "C160") (pin "2") (pinfunction "2_2") (pintype "passive"))
      (node (ref "C161") (pin "2") (pinfunction "2_2") (pintype "passive"))
      (node (ref "C162") (pin "2") (pinfunction "2_2") (pintype "passive"))
      (node (ref "C163") (pin "2") (pinfunction "2_2") (pintype "passive"))
      (node (ref "C176") (pin "1") (pinfunction "1_1") (pintype "passive"))
      (node (ref "C177") (pin "1") (pinfunction "1_1") (pintype "passive"))
      (node (ref "C178") (pin "1") (pinfunction "1_1") (pintype "passive"))
      (node (ref "C179") (pin "1") (pinfunction "1_1") (pintype "passive"))
      (node (ref "C180") (pin "1") (pinfunction "1_1") (pintype "passive"))
      (node (ref "C181") (pin "1") (pinfunction "1_1") (pintype "passive"))
      (node (ref "C182") (pin "1") (pinfunction "1_1") (pintype "passive"))
      (node (ref "C183") (pin "1") (pinfunction "1_1") (pintype "passive"))
      (node (ref "C184") (pin "1") (pinfunction "1_1") (pintype "passive"))
      (node (ref "C185") (pin "1") (pinfunction "1_1") (pintype "passive"))
      (node (ref "C186") (pin "1") (pinfunction "1_1") (pintype "passive"))
      (node (ref "C187") (pin "1") (pinfunction "1_1") (pintype "passive"))
      (node (ref "C429") (pin "1") (pinfunction "1_1") (pintype "passive"))
      (node (ref "R1") (pin "2") (pinfunction "2_2") (pintype "passive"))
      (node (ref "R2") (pin "2") (pinfunction "2_2") (pintype "passive"))
      (node (ref "R23") (pin "2") (pinfunction "2_2") (pintype "passive"))
      (node (ref "TP74") (pin "1") (pinfunction "1_1") (pintype "passive"))
      (node (ref "TP75") (pin "1") (pinfunction "1_1") (pintype "passive"))
      (node (ref "TP76") (pin "1") (pinfunction "1_1") (pintype "passive"))
      (node (ref "TP77") (pin "1") (pinfunction "1_1") (pintype "passive"))
      (node (ref "U2") (pin "AF2") (pinfunction "ANAVSS_DIO_1_AF2") (pintype "passive"))
      (node (ref "U2") (pin "AF6") (pinfunction "ANAVSS_PLL_1_AF6") (pintype "passive"))
      (node (ref "U2") (pin "AL26") (pinfunction "ANAVSS_PLL_2_AL26") (pintype "passive"))
      (node (ref "U2") (pin "AR26") (pinfunction "ANAVSS_DIO_2_AR26") (pintype "passive"))
      (node (ref "U2") (pin "B11") (pinfunction "ANAVSS_DIO_4_B11") (pintype "passive"))
      (node (ref "U2") (pin "F11") (pinfunction "ANAVSS_PLL_4_F11") (pintype "passive"))
      (node (ref "U2") (pin "L31") (pinfunction "ANAVSS_PLL_3_L31") (pintype "passive"))
      (node (ref "U2") (pin "L35") (pinfunction "ANAVSS_DIO_3_L35") (pintype "passive"))
      (node (ref "Y3") (pin "2") (pinfunction "GND_2") (pintype "passive"))
    )
    (net (code "22") (name "Net-(U2B-ANAVDD_DIO_1)") (class "Default")
      (node (ref "R31") (pin "2") (pinfunction "2_2") (pintype "passive"))
      (node (ref "TP82") (pin "1") (pinfunction "1_1") (pintype "passive"))
      (node (ref "U2") (pin "AE4") (pinfunction "ANAVDD_DIO_1_AE4") (pintype "passive"))
    )
    (net (code "23") (name "Net-(U2B-DBG_HEART_BEAT_1)") (class "Default")
      (node (ref "TP54") (pin "1") (pinfunction "1_1") (pintype "passive"))
      (node (ref "U2") (pin "AM1") (pinfunction "DBG_HEART_BEAT_1_AM1") (pintype "passive"))
    )
    (net (code "24") (name "Net-(U2B-DBG_PLL_FBSLIP_1)") (class "Default")
      (node (ref "TP62") (pin "1") (pinfunction "1_1") (pintype "passive"))
      (node (ref "U2") (pin "AH3") (pinfunction "DBG_PLL_FBSLIP_1_AH3") (pintype "passive"))
    )
    (net (code "25") (name "Net-(U2B-DBG_PLL_LOST_LOCK_1)") (class "Default")
      (node (ref "TP66") (pin "1") (pinfunction "1_1") (pintype "passive"))
      (node (ref "U2") (pin "AG4") (pinfunction "DBG_PLL_LOST_LOCK_1_AG4") (pintype "passive"))
    )
    (net (code "26") (name "Net-(U2B-DBG_PLL_RFSLIP_1)") (class "Default")
      (node (ref "TP58") (pin "1") (pinfunction "1_1") (pintype "passive"))
      (node (ref "U2") (pin "AG2") (pinfunction "DBG_PLL_RFSLIP_1_AG2") (pintype "passive"))
    )
    (net (code "27") (name "Net-(U2B-VDD_SENSE_1)") (class "Default")
      (node (ref "TP34") (pin "1") (pinfunction "1_1") (pintype "passive"))
      (node (ref "U2") (pin "AM7") (pinfunction "VDD_SENSE_1_AM7") (pintype "passive"))
    )
    (net (code "28") (name "Net-(U2B-VSS_SENSE_1)") (class "Default")
      (node (ref "TP30") (pin "1") (pinfunction "1_1") (pintype "passive"))
      (node (ref "U2") (pin "AM6") (pinfunction "VSS_SENSE_1_AM6") (pintype "passive"))
    )
    (net (code "29") (name "Net-(U2C-ANAVDD_DIO_2)") (class "Default")
      (node (ref "R32") (pin "2") (pinfunction "2_2") (pintype "passive"))
      (node (ref "TP83") (pin "1") (pinfunction "1_1") (pintype "passive"))
      (node (ref "U2") (pin "AN25") (pinfunction "ANAVDD_DIO_2_AN25") (pintype "passive"))
    )
    (net (code "30") (name "Net-(U2C-DBG_HEART_BEAT_2)") (class "Default")
      (node (ref "TP55") (pin "1") (pinfunction "1_1") (pintype "passive"))
      (node (ref "U2") (pin "AT32") (pinfunction "DBG_HEART_BEAT_2_AT32") (pintype "passive"))
    )
    (net (code "31") (name "Net-(U2C-DBG_PLL_FBSLIP_2)") (class "Default")
      (node (ref "TP63") (pin "1") (pinfunction "1_1") (pintype "passive"))
      (node (ref "U2") (pin "AP28") (pinfunction "DBG_PLL_FBSLIP_2_AP28") (pintype "passive"))
    )
    (net (code "32") (name "Net-(U2C-DBG_PLL_LOST_LOCK_2)") (class "Default")
      (node (ref "TP67") (pin "1") (pinfunction "1_1") (pintype "passive"))
      (node (ref "U2") (pin "AN27") (pinfunction "DBG_PLL_LOST_LOCK_2_AN27") (pintype "passive"))
    )
    (net (code "33") (name "Net-(U2C-DBG_PLL_RFSLIP_2)") (class "Default")
      (node (ref "TP59") (pin "1") (pinfunction "1_1") (pintype "passive"))
      (node (ref "U2") (pin "AR27") (pinfunction "DBG_PLL_RFSLIP_2_AR27") (pintype "passive"))
    )
    (net (code "34") (name "Net-(U2C-VDD_SENSE_2)") (class "Default")
      (node (ref "TP35") (pin "1") (pinfunction "1_1") (pintype "passive"))
      (node (ref "U2") (pin "AK32") (pinfunction "VDD_SENSE_2_AK32") (pintype "passive"))
    )
    (net (code "35") (name "Net-(U2C-VSS_SENSE_2)") (class "Default")
      (node (ref "TP31") (pin "1") (pinfunction "1_1") (pintype "passive"))
      (node (ref "U2") (pin "AL32") (pinfunction "VSS_SENSE_2_AL32") (pintype "passive"))
    )
    (net (code "36") (name "Net-(U2D-ANAVDD_DIO_3)") (class "Default")
      (node (ref "R33") (pin "2") (pinfunction "2_2") (pintype "passive"))
      (node (ref "TP84") (pin "1") (pinfunction "1_1") (pintype "passive"))
      (node (ref "U2") (pin "M33") (pinfunction "ANAVDD_DIO_3_M33") (pintype "passive"))
    )
    (net (code "37") (name "Net-(U2D-DBG_HEART_BEAT_3)") (class "Default")
      (node (ref "TP56") (pin "1") (pinfunction "1_1") (pintype "passive"))
      (node (ref "U2") (pin "E36") (pinfunction "DBG_HEART_BEAT_3_E36") (pintype "passive"))
    )
    (net (code "38") (name "Net-(U2D-DBG_PLL_FBSLIP_3)") (class "Default")
      (node (ref "TP64") (pin "1") (pinfunction "1_1") (pintype "passive"))
      (node (ref "U2") (pin "J34") (pinfunction "DBG_PLL_FBSLIP_3_J34") (pintype "passive"))
    )
    (net (code "39") (name "Net-(U2D-DBG_PLL_LOST_LOCK_3)") (class "Default")
      (node (ref "TP68") (pin "1") (pinfunction "1_1") (pintype "passive"))
      (node (ref "U2") (pin "K33") (pinfunction "DBG_PLL_LOST_LOCK_3_K33") (pintype "passive"))
    )
    (net (code "40") (name "Net-(U2D-DBG_PLL_RFSLIP_3)") (class "Default")
      (node (ref "TP60") (pin "1") (pinfunction "1_1") (pintype "passive"))
      (node (ref "U2") (pin "K35") (pinfunction "DBG_PLL_RFSLIP_3_K35") (pintype "passive"))
    )
    (net (code "41") (name "Net-(U2D-VDD_SENSE_3)") (class "Default")
      (node (ref "TP36") (pin "1") (pinfunction "1_1") (pintype "passive"))
      (node (ref "U2") (pin "E30") (pinfunction "VDD_SENSE_3_E30") (pintype "passive"))
    )
    (net (code "42") (name "Net-(U2D-VSS_SENSE_3)") (class "Default")
      (node (ref "TP32") (pin "1") (pinfunction "1_1") (pintype "passive"))
      (node (ref "U2") (pin "E31") (pinfunction "VSS_SENSE_3_E31") (pintype "passive"))
    )
    (net (code "43") (name "Net-(U2E-ANAVDD_DIO_4)") (class "Default")
      (node (ref "R34") (pin "2") (pinfunction "2_2") (pintype "passive"))
      (node (ref "TP85") (pin "1") (pinfunction "1_1") (pintype "passive"))
      (node (ref "U2") (pin "D12") (pinfunction "ANAVDD_DIO_4_D12") (pintype "passive"))
    )
    (net (code "44") (name "Net-(U2E-DBG_HEART_BEAT_4)") (class "Default")
      (node (ref "TP57") (pin "1") (pinfunction "1_1") (pintype "passive"))
      (node (ref "U2") (pin "A5") (pinfunction "DBG_HEART_BEAT_4_A5") (pintype "passive"))
    )
    (net (code "45") (name "Net-(U2E-DBG_PLL_FBSLIP_4)") (class "Default")
      (node (ref "TP65") (pin "1") (pinfunction "1_1") (pintype "passive"))
      (node (ref "U2") (pin "C9") (pinfunction "DBG_PLL_FBSLIP_4_C9") (pintype "passive"))
    )
    (net (code "46") (name "Net-(U2E-DBG_PLL_LOST_LOCK_4)") (class "Default")
      (node (ref "TP69") (pin "1") (pinfunction "1_1") (pintype "passive"))
      (node (ref "U2") (pin "D10") (pinfunction "DBG_PLL_LOST_LOCK_4_D10") (pintype "passive"))
    )
    (net (code "47") (name "Net-(U2E-DBG_PLL_RFSLIP_4)") (class "Default")
      (node (ref "TP61") (pin "1") (pinfunction "1_1") (pintype "passive"))
      (node (ref "U2") (pin "B10") (pinfunction "DBG_PLL_RFSLIP_4_B10") (pintype "passive"))
    )
    (net (code "48") (name "Net-(U2E-VDD_SENSE_4)") (class "Default")
      (node (ref "TP37") (pin "1") (pinfunction "1_1") (pintype "passive"))
      (node (ref "U2") (pin "G5") (pinfunction "VDD_SENSE_4_G5") (pintype "passive"))
    )
    (net (code "49") (name "Net-(U2E-VSS_SENSE_4)") (class "Default")
      (node (ref "TP33") (pin "1") (pinfunction "1_1") (pintype "passive"))
      (node (ref "U2") (pin "F5") (pinfunction "VSS_SENSE_4_F5") (pintype "passive"))
    )
    (net (code "50") (name "unconnected-(U2B-DBG_SPARE[0]_1-PadAE3)") (class "Default")
      (node (ref "U2") (pin "AE3") (pinfunction "DBG_SPARE[0]_1_AE3") (pintype "passive+no_connect"))
    )
    (net (code "51") (name "unconnected-(U2B-DBG_SPARE[1]_1-PadAE2)") (class "Default")
      (node (ref "U2") (pin "AE2") (pinfunction "DBG_SPARE[1]_1_AE2") (pintype "passive+no_connect"))
    )
    (net (code "52") (name "unconnected-(U2B-JTG_TCK_1-PadAN11)") (class "Default")
      (node (ref "U2") (pin "AN11") (pinfunction "JTG_TCK_1_AN11") (pintype "passive+no_connect"))
    )
    (net (code "53") (name "unconnected-(U2B-JTG_TDI_1-PadAT11)") (class "Default")
      (node (ref "U2") (pin "AT11") (pinfunction "JTG_TDI_1_AT11") (pintype "passive+no_connect"))
    )
    (net (code "54") (name "unconnected-(U2B-JTG_TDO_1-PadAP12)") (class "Default")
      (node (ref "U2") (pin "AP12") (pinfunction "JTG_TDO_1_AP12") (pintype "passive+no_connect"))
    )
    (net (code "55") (name "unconnected-(U2B-JTG_TMS_1-PadAT12)") (class "Default")
      (node (ref "U2") (pin "AT12") (pinfunction "JTG_TMS_1_AT12") (pintype "passive+no_connect"))
    )
    (net (code "56") (name "unconnected-(U2B-TEST_GPIO[0]_1-PadAR18)") (class "Default")
      (node (ref "U2") (pin "AR18") (pinfunction "TEST_GPIO[0]_1_AR18") (pintype "passive+no_connect"))
    )
    (net (code "57") (name "unconnected-(U2B-TEST_GPIO[1]_1-PadAR17)") (class "Default")
      (node (ref "U2") (pin "AR17") (pinfunction "TEST_GPIO[1]_1_AR17") (pintype "passive+no_connect"))
    )
    (net (code "58") (name "unconnected-(U2B-TEST_GPIO[2]_1-PadAP17)") (class "Default")
      (node (ref "U2") (pin "AP17") (pinfunction "TEST_GPIO[2]_1_AP17") (pintype "passive+no_connect"))
    )
    (net (code "59") (name "unconnected-(U2B-TEST_GPIO[3]_1-PadAT17)") (class "Default")
      (node (ref "U2") (pin "AT17") (pinfunction "TEST_GPIO[3]_1_AT17") (pintype "passive+no_connect"))
    )
    (net (code "60") (name "unconnected-(U2B-TEST_GPIO[4]_1-PadAN16)") (class "Default")
      (node (ref "U2") (pin "AN16") (pinfunction "TEST_GPIO[4]_1_AN16") (pintype "passive+no_connect"))
    )
    (net (code "61") (name "unconnected-(U2B-TEST_GPIO[5]_1-PadAT16)") (class "Default")
      (node (ref "U2") (pin "AT16") (pinfunction "TEST_GPIO[5]_1_AT16") (pintype "passive+no_connect"))
    )
    (net (code "62") (name "unconnected-(U2B-TEST_GPIO[6]_1-PadAP16)") (class "Default")
      (node (ref "U2") (pin "AP16") (pinfunction "TEST_GPIO[6]_1_AP16") (pintype "passive+no_connect"))
    )
    (net (code "63") (name "unconnected-(U2B-TEST_GPIO[7]_1-PadAN15)") (class "Default")
      (node (ref "U2") (pin "AN15") (pinfunction "TEST_GPIO[7]_1_AN15") (pintype "passive+no_connect"))
    )
    (net (code "64") (name "unconnected-(U2B-TEST_GPIO[8]_1-PadAP15)") (class "Default")
      (node (ref "U2") (pin "AP15") (pinfunction "TEST_GPIO[8]_1_AP15") (pintype "passive+no_connect"))
    )
    (net (code "65") (name "unconnected-(U2B-TEST_GPIO[9]_1-PadAT15)") (class "Default")
      (node (ref "U2") (pin "AT15") (pinfunction "TEST_GPIO[9]_1_AT15") (pintype "passive+no_connect"))
    )
    (net (code "66") (name "unconnected-(U2B-TEST_GPIO[10]_1-PadAR15)") (class "Default")
      (node (ref "U2") (pin "AR15") (pinfunction "TEST_GPIO[10]_1_AR15") (pintype "passive+no_connect"))
    )
    (net (code "67") (name "unconnected-(U2B-TEST_GPIO[11]_1-PadAN14)") (class "Default")
      (node (ref "U2") (pin "AN14") (pinfunction "TEST_GPIO[11]_1_AN14") (pintype "passive+no_connect"))
    )
    (net (code "68") (name "unconnected-(U2B-TEST_GPIO[12]_1-PadAR14)") (class "Default")
      (node (ref "U2") (pin "AR14") (pinfunction "TEST_GPIO[12]_1_AR14") (pintype "passive+no_connect"))
    )
    (net (code "69") (name "unconnected-(U2B-TEST_GPIO[13]_1-PadAR13)") (class "Default")
      (node (ref "U2") (pin "AR13") (pinfunction "TEST_GPIO[13]_1_AR13") (pintype "passive+no_connect"))
    )
    (net (code "70") (name "unconnected-(U2B-TEST_GPIO[14]_1-PadAT14)") (class "Default")
      (node (ref "U2") (pin "AT14") (pinfunction "TEST_GPIO[14]_1_AT14") (pintype "passive+no_connect"))
    )
    (net (code "71") (name "unconnected-(U2B-TEST_GPIO[15]_1-PadAP13)") (class "Default")
      (node (ref "U2") (pin "AP13") (pinfunction "TEST_GPIO[15]_1_AP13") (pintype "passive+no_connect"))
    )
    (net (code "72") (name "unconnected-(U2B-TEST_GPIO[16]_1-PadAP11)") (class "Default")
      (node (ref "U2") (pin "AP11") (pinfunction "TEST_GPIO[16]_1_AP11") (pintype "passive+no_connect"))
    )
    (net (code "73") (name "unconnected-(U2B-TEST_GPIO[17]_1-PadAT10)") (class "Default")
      (node (ref "U2") (pin "AT10") (pinfunction "TEST_GPIO[17]_1_AT10") (pintype "passive+no_connect"))
    )
    (net (code "74") (name "unconnected-(U2B-TEST_GPIO[18]_1-PadAR10)") (class "Default")
      (node (ref "U2") (pin "AR10") (pinfunction "TEST_GPIO[18]_1_AR10") (pintype "passive+no_connect"))
    )
    (net (code "75") (name "unconnected-(U2B-TEST_GPIO[19]_1-PadAN10)") (class "Default")
      (node (ref "U2") (pin "AN10") (pinfunction "TEST_GPIO[19]_1_AN10") (pintype "passive+no_connect"))
    )
    (net (code "76") (name "unconnected-(U2B-TEST_GPIO[20]_1-PadAP10)") (class "Default")
      (node (ref "U2") (pin "AP10") (pinfunction "TEST_GPIO[20]_1_AP10") (pintype "passive+no_connect"))
    )
    (net (code "77") (name "unconnected-(U2B-TEST_GPIO[21]_1-PadAT9)") (class "Default")
      (node (ref "U2") (pin "AT9") (pinfunction "TEST_GPIO[21]_1_AT9") (pintype "passive+no_connect"))
    )
    (net (code "78") (name "unconnected-(U2B-TEST_GPIO[22]_1-PadAR9)") (class "Default")
      (node (ref "U2") (pin "AR9") (pinfunction "TEST_GPIO[22]_1_AR9") (pintype "passive+no_connect"))
    )
    (net (code "79") (name "unconnected-(U2B-TEST_GPIO[23]_1-PadAR8)") (class "Default")
      (node (ref "U2") (pin "AR8") (pinfunction "TEST_GPIO[23]_1_AR8") (pintype "passive+no_connect"))
    )
    (net (code "80") (name "unconnected-(U2B-TEST_GPIO[24]_1-PadAN9)") (class "Default")
      (node (ref "U2") (pin "AN9") (pinfunction "TEST_GPIO[24]_1_AN9") (pintype "passive+no_connect"))
    )
    (net (code "81") (name "unconnected-(U2B-TEST_GPIO[25]_1-PadAP8)") (class "Default")
      (node (ref "U2") (pin "AP8") (pinfunction "TEST_GPIO[25]_1_AP8") (pintype "passive+no_connect"))
    )
    (net (code "82") (name "unconnected-(U2B-TEST_GPIO[26]_1-PadAN8)") (class "Default")
      (node (ref "U2") (pin "AN8") (pinfunction "TEST_GPIO[26]_1_AN8") (pintype "passive+no_connect"))
    )
    (net (code "83") (name "unconnected-(U2B-TEST_GPIO[27]_1-PadAR7)") (class "Default")
      (node (ref "U2") (pin "AR7") (pinfunction "TEST_GPIO[27]_1_AR7") (pintype "passive+no_connect"))
    )
    (net (code "84") (name "unconnected-(U2B-TEST_GPIO[28]_1-PadAT7)") (class "Default")
      (node (ref "U2") (pin "AT7") (pinfunction "TEST_GPIO[28]_1_AT7") (pintype "passive+no_connect"))
    )
    (net (code "85") (name "unconnected-(U2B-TEST_GPIO[29]_1-PadAP7)") (class "Default")
      (node (ref "U2") (pin "AP7") (pinfunction "TEST_GPIO[29]_1_AP7") (pintype "passive+no_connect"))
    )
    (net (code "86") (name "unconnected-(U2B-TEST_GPIO[30]_1-PadAT6)") (class "Default")
      (node (ref "U2") (pin "AT6") (pinfunction "TEST_GPIO[30]_1_AT6") (pintype "passive+no_connect"))
    )
    (net (code "87") (name "unconnected-(U2B-TEST_GPIO[31]_1-PadAT5)") (class "Default")
      (node (ref "U2") (pin "AT5") (pinfunction "TEST_GPIO[31]_1_AT5") (pintype "passive+no_connect"))
    )
    (net (code "88") (name "unconnected-(U2B-TEST_GPIO[32]_1-PadAP6)") (class "Default")
      (node (ref "U2") (pin "AP6") (pinfunction "TEST_GPIO[32]_1_AP6") (pintype "passive+no_connect"))
    )
    (net (code "89") (name "unconnected-(U2B-TEST_GPIO[33]_1-PadAN6)") (class "Default")
      (node (ref "U2") (pin "AN6") (pinfunction "TEST_GPIO[33]_1_AN6") (pintype "passive+no_connect"))
    )
    (net (code "90") (name "unconnected-(U2B-TEST_GPIO[34]_1-PadAN5)") (class "Default")
      (node (ref "U2") (pin "AN5") (pinfunction "TEST_GPIO[34]_1_AN5") (pintype "passive+no_connect"))
    )
    (net (code "91") (name "unconnected-(U2B-TEST_GPIO[35]_1-PadAT4)") (class "Default")
      (node (ref "U2") (pin "AT4") (pinfunction "TEST_GPIO[35]_1_AT4") (pintype "passive+no_connect"))
    )
    (net (code "92") (name "unconnected-(U2B-TEST_GPIO[36]_1-PadAR4)") (class "Default")
      (node (ref "U2") (pin "AR4") (pinfunction "TEST_GPIO[36]_1_AR4") (pintype "passive+no_connect"))
    )
    (net (code "93") (name "unconnected-(U2B-TEST_GPIO[37]_1-PadAN4)") (class "Default")
      (node (ref "U2") (pin "AN4") (pinfunction "TEST_GPIO[37]_1_AN4") (pintype "passive+no_connect"))
    )
    (net (code "94") (name "unconnected-(U2B-TEST_GPIO[38]_1-PadAR3)") (class "Default")
      (node (ref "U2") (pin "AR3") (pinfunction "TEST_GPIO[38]_1_AR3") (pintype "passive+no_connect"))
    )
    (net (code "95") (name "unconnected-(U2B-TEST_GPIO[39]_1-PadAM4)") (class "Default")
      (node (ref "U2") (pin "AM4") (pinfunction "TEST_GPIO[39]_1_AM4") (pintype "passive+no_connect"))
    )
    (net (code "96") (name "unconnected-(U2B-TEST_GPIO[40]_1-PadAP3)") (class "Default")
      (node (ref "U2") (pin "AP3") (pinfunction "TEST_GPIO[40]_1_AP3") (pintype "passive+no_connect"))
    )
    (net (code "97") (name "unconnected-(U2B-TEST_GPIO[41]_1-PadAN3)") (class "Default")
      (node (ref "U2") (pin "AN3") (pinfunction "TEST_GPIO[41]_1_AN3") (pintype "passive+no_connect"))
    )
    (net (code "98") (name "unconnected-(U2B-TEST_GPIO[42]_1-PadAR2)") (class "Default")
      (node (ref "U2") (pin "AR2") (pinfunction "TEST_GPIO[42]_1_AR2") (pintype "passive+no_connect"))
    )
    (net (code "99") (name "unconnected-(U2B-TEST_GPIO[43]_1-PadAL4)") (class "Default")
      (node (ref "U2") (pin "AL4") (pinfunction "TEST_GPIO[43]_1_AL4") (pintype "passive+no_connect"))
    )
    (net (code "100") (name "unconnected-(U2B-TEST_GPIO[44]_1-PadAM3)") (class "Default")
      (node (ref "U2") (pin "AM3") (pinfunction "TEST_GPIO[44]_1_AM3") (pintype "passive+no_connect"))
    )
    (net (code "101") (name "unconnected-(U2B-TEST_GPIO[45]_1-PadAP2)") (class "Default")
      (node (ref "U2") (pin "AP2") (pinfunction "TEST_GPIO[45]_1_AP2") (pintype "passive+no_connect"))
    )
    (net (code "102") (name "unconnected-(U2B-TEST_GPIO[46]_1-PadAP1)") (class "Default")
      (node (ref "U2") (pin "AP1") (pinfunction "TEST_GPIO[46]_1_AP1") (pintype "passive+no_connect"))
    )
    (net (code "103") (name "unconnected-(U2B-TEST_GPIO[47]_1-PadAK4)") (class "Default")
      (node (ref "U2") (pin "AK4") (pinfunction "TEST_GPIO[47]_1_AK4") (pintype "passive+no_connect"))
    )
    (net (code "104") (name "unconnected-(U2B-TEST_GPIO[48]_1-PadAM2)") (class "Default")
      (node (ref "U2") (pin "AM2") (pinfunction "TEST_GPIO[48]_1_AM2") (pintype "passive+no_connect"))
    )
    (net (code "105") (name "unconnected-(U2B-TEST_GPIO[49]_1-PadAN1)") (class "Default")
      (node (ref "U2") (pin "AN1") (pinfunction "TEST_GPIO[49]_1_AN1") (pintype "passive+no_connect"))
    )
    (net (code "106") (name "unconnected-(U2B-TEST_GPIO[50]_1-PadAK3)") (class "Default")
      (node (ref "U2") (pin "AK3") (pinfunction "TEST_GPIO[50]_1_AK3") (pintype "passive+no_connect"))
    )
    (net (code "107") (name "unconnected-(U2B-TEST_GPIO[51]_1-PadAL2)") (class "Default")
      (node (ref "U2") (pin "AL2") (pinfunction "TEST_GPIO[51]_1_AL2") (pintype "passive+no_connect"))
    )
    (net (code "108") (name "unconnected-(U2B-TEST_GPIO[52]_1-PadAD3)") (class "Default")
      (node (ref "U2") (pin "AD3") (pinfunction "TEST_GPIO[52]_1_AD3") (pintype "passive+no_connect"))
    )
    (net (code "109") (name "unconnected-(U2B-TEST_GPIO[53]_1-PadAD2)") (class "Default")
      (node (ref "U2") (pin "AD2") (pinfunction "TEST_GPIO[53]_1_AD2") (pintype "passive+no_connect"))
    )
    (net (code "110") (name "unconnected-(U2B-TEST_GPIO[54]_1-PadAC3)") (class "Default")
      (node (ref "U2") (pin "AC3") (pinfunction "TEST_GPIO[54]_1_AC3") (pintype "passive+no_connect"))
    )
    (net (code "111") (name "unconnected-(U2B-TEST_GPIO[55]_1-PadAC4)") (class "Default")
      (node (ref "U2") (pin "AC4") (pinfunction "TEST_GPIO[55]_1_AC4") (pintype "passive+no_connect"))
    )
    (net (code "112") (name "unconnected-(U2B-TEST_GPIO[56]_1-PadAD1)") (class "Default")
      (node (ref "U2") (pin "AD1") (pinfunction "TEST_GPIO[56]_1_AD1") (pintype "passive+no_connect"))
    )
    (net (code "113") (name "unconnected-(U2B-TEST_GPIO[57]_1-PadAC1)") (class "Default")
      (node (ref "U2") (pin "AC1") (pinfunction "TEST_GPIO[57]_1_AC1") (pintype "passive+no_connect"))
    )
    (net (code "114") (name "unconnected-(U2B-TEST_GPIO[58]_1-PadAB3)") (class "Default")
      (node (ref "U2") (pin "AB3") (pinfunction "TEST_GPIO[58]_1_AB3") (pintype "passive+no_connect"))
    )
    (net (code "115") (name "unconnected-(U2B-TEST_GPIO[59]_1-PadAB4)") (class "Default")
      (node (ref "U2") (pin "AB4") (pinfunction "TEST_GPIO[59]_1_AB4") (pintype "passive+no_connect"))
    )
    (net (code "116") (name "unconnected-(U2B-TEST_GPIO[60]_1-PadAB2)") (class "Default")
      (node (ref "U2") (pin "AB2") (pinfunction "TEST_GPIO[60]_1_AB2") (pintype "passive+no_connect"))
    )
    (net (code "117") (name "unconnected-(U2B-TEST_GPIO[61]_1-PadAA1)") (class "Default")
      (node (ref "U2") (pin "AA1") (pinfunction "TEST_GPIO[61]_1_AA1") (pintype "passive+no_connect"))
    )
    (net (code "118") (name "unconnected-(U2B-TEST_GPIO[62]_1-PadAB1)") (class "Default")
      (node (ref "U2") (pin "AB1") (pinfunction "TEST_GPIO[62]_1_AB1") (pintype "passive+no_connect"))
    )
    (net (code "119") (name "unconnected-(U2B-TEST_GPIO[63]_1-PadAA2)") (class "Default")
      (node (ref "U2") (pin "AA2") (pinfunction "TEST_GPIO[63]_1_AA2") (pintype "passive+no_connect"))
    )
    (net (code "120") (name "unconnected-(U2B-TEST_GPIO[64]_1-PadAA4)") (class "Default")
      (node (ref "U2") (pin "AA4") (pinfunction "TEST_GPIO[64]_1_AA4") (pintype "passive+no_connect"))
    )
    (net (code "121") (name "unconnected-(U2B-TEST_GPIO[65]_1-PadY3)") (class "Default")
      (node (ref "U2") (pin "Y3") (pinfunction "TEST_GPIO[65]_1_Y3") (pintype "passive+no_connect"))
    )
    (net (code "122") (name "unconnected-(U2B-TEST_GPIO[66]_1-PadY2)") (class "Default")
      (node (ref "U2") (pin "Y2") (pinfunction "TEST_GPIO[66]_1_Y2") (pintype "passive+no_connect"))
    )
    (net (code "123") (name "unconnected-(U2B-TEST_GPIO[67]_1-PadY4)") (class "Default")
      (node (ref "U2") (pin "Y4") (pinfunction "TEST_GPIO[67]_1_Y4") (pintype "passive+no_connect"))
    )
    (net (code "124") (name "unconnected-(U2B-TEST_GPIO[68]_1-PadW1)") (class "Default")
      (node (ref "U2") (pin "W1") (pinfunction "TEST_GPIO[68]_1_W1") (pintype "passive+no_connect"))
    )
    (net (code "125") (name "unconnected-(U2B-TEST_GPIO[69]_1-PadW3)") (class "Default")
      (node (ref "U2") (pin "W3") (pinfunction "TEST_GPIO[69]_1_W3") (pintype "passive+no_connect"))
    )
    (net (code "126") (name "unconnected-(U2B-TEST_GPIO[70]_1-PadW2)") (class "Default")
      (node (ref "U2") (pin "W2") (pinfunction "TEST_GPIO[70]_1_W2") (pintype "passive+no_connect"))
    )
    (net (code "127") (name "unconnected-(U2B-TEST_GPIO[71]_1-PadW5)") (class "Default")
      (node (ref "U2") (pin "W5") (pinfunction "TEST_GPIO[71]_1_W5") (pintype "passive+no_connect"))
    )
    (net (code "128") (name "unconnected-(U2C-DBG_SPARE[0]_2-PadAP25)") (class "Default")
      (node (ref "U2") (pin "AP25") (pinfunction "DBG_SPARE[0]_2_AP25") (pintype "passive+no_connect"))
    )
    (net (code "129") (name "unconnected-(U2C-DBG_SPARE[1]_2-PadAR25)") (class "Default")
      (node (ref "U2") (pin "AR25") (pinfunction "DBG_SPARE[1]_2_AR25") (pintype "passive+no_connect"))
    )
    (net (code "130") (name "unconnected-(U2C-JTG_TCK_2-PadAF33)") (class "Default")
      (node (ref "U2") (pin "AF33") (pinfunction "JTG_TCK_2_AF33") (pintype "passive+no_connect"))
    )
    (net (code "131") (name "unconnected-(U2C-JTG_TDI_2-PadAF36)") (class "Default")
      (node (ref "U2") (pin "AF36") (pinfunction "JTG_TDI_2_AF36") (pintype "passive+no_connect"))
    )
    (net (code "132") (name "unconnected-(U2C-JTG_TDO_2-PadAE34)") (class "Default")
      (node (ref "U2") (pin "AE34") (pinfunction "JTG_TDO_2_AE34") (pintype "passive+no_connect"))
    )
    (net (code "133") (name "unconnected-(U2C-JTG_TMS_2-PadAE36)") (class "Default")
      (node (ref "U2") (pin "AE36") (pinfunction "JTG_TMS_2_AE36") (pintype "passive+no_connect"))
    )
    (net (code "134") (name "unconnected-(U2C-TEST_GPIO[0]_2-PadW35)") (class "Default")
      (node (ref "U2") (pin "W35") (pinfunction "TEST_GPIO[0]_2_W35") (pintype "passive+no_connect"))
    )
    (net (code "135") (name "unconnected-(U2C-TEST_GPIO[1]_2-PadY35)") (class "Default")
      (node (ref "U2") (pin "Y35") (pinfunction "TEST_GPIO[1]_2_Y35") (pintype "passive+no_connect"))
    )
    (net (code "136") (name "unconnected-(U2C-TEST_GPIO[2]_2-PadY34)") (class "Default")
      (node (ref "U2") (pin "Y34") (pinfunction "TEST_GPIO[2]_2_Y34") (pintype "passive+no_connect"))
    )
    (net (code "137") (name "unconnected-(U2C-TEST_GPIO[3]_2-PadY36)") (class "Default")
      (node (ref "U2") (pin "Y36") (pinfunction "TEST_GPIO[3]_2_Y36") (pintype "passive+no_connect"))
    )
    (net (code "138") (name "unconnected-(U2C-TEST_GPIO[4]_2-PadAA33)") (class "Default")
      (node (ref "U2") (pin "AA33") (pinfunction "TEST_GPIO[4]_2_AA33") (pintype "passive+no_connect"))
    )
    (net (code "139") (name "unconnected-(U2C-TEST_GPIO[5]_2-PadAA36)") (class "Default")
      (node (ref "U2") (pin "AA36") (pinfunction "TEST_GPIO[5]_2_AA36") (pintype "passive+no_connect"))
    )
    (net (code "140") (name "unconnected-(U2C-TEST_GPIO[6]_2-PadAA34)") (class "Default")
      (node (ref "U2") (pin "AA34") (pinfunction "TEST_GPIO[6]_2_AA34") (pintype "passive+no_connect"))
    )
    (net (code "141") (name "unconnected-(U2C-TEST_GPIO[7]_2-PadAB33)") (class "Default")
      (node (ref "U2") (pin "AB33") (pinfunction "TEST_GPIO[7]_2_AB33") (pintype "passive+no_connect"))
    )
    (net (code "142") (name "unconnected-(U2C-TEST_GPIO[8]_2-PadAB34)") (class "Default")
      (node (ref "U2") (pin "AB34") (pinfunction "TEST_GPIO[8]_2_AB34") (pintype "passive+no_connect"))
    )
    (net (code "143") (name "unconnected-(U2C-TEST_GPIO[9]_2-PadAB36)") (class "Default")
      (node (ref "U2") (pin "AB36") (pinfunction "TEST_GPIO[9]_2_AB36") (pintype "passive+no_connect"))
    )
    (net (code "144") (name "unconnected-(U2C-TEST_GPIO[10]_2-PadAB35)") (class "Default")
      (node (ref "U2") (pin "AB35") (pinfunction "TEST_GPIO[10]_2_AB35") (pintype "passive+no_connect"))
    )
    (net (code "145") (name "unconnected-(U2C-TEST_GPIO[11]_2-PadAC33)") (class "Default")
      (node (ref "U2") (pin "AC33") (pinfunction "TEST_GPIO[11]_2_AC33") (pintype "passive+no_connect"))
    )
    (net (code "146") (name "unconnected-(U2C-TEST_GPIO[12]_2-PadAC35)") (class "Default")
      (node (ref "U2") (pin "AC35") (pinfunction "TEST_GPIO[12]_2_AC35") (pintype "passive+no_connect"))
    )
    (net (code "147") (name "unconnected-(U2C-TEST_GPIO[13]_2-PadAD35)") (class "Default")
      (node (ref "U2") (pin "AD35") (pinfunction "TEST_GPIO[13]_2_AD35") (pintype "passive+no_connect"))
    )
    (net (code "148") (name "unconnected-(U2C-TEST_GPIO[14]_2-PadAC36)") (class "Default")
      (node (ref "U2") (pin "AC36") (pinfunction "TEST_GPIO[14]_2_AC36") (pintype "passive+no_connect"))
    )
    (net (code "149") (name "unconnected-(U2C-TEST_GPIO[15]_2-PadAD34)") (class "Default")
      (node (ref "U2") (pin "AD34") (pinfunction "TEST_GPIO[15]_2_AD34") (pintype "passive+no_connect"))
    )
    (net (code "150") (name "unconnected-(U2C-TEST_GPIO[16]_2-PadAF34)") (class "Default")
      (node (ref "U2") (pin "AF34") (pinfunction "TEST_GPIO[16]_2_AF34") (pintype "passive+no_connect"))
    )
    (net (code "151") (name "unconnected-(U2C-TEST_GPIO[17]_2-PadAG36)") (class "Default")
      (node (ref "U2") (pin "AG36") (pinfunction "TEST_GPIO[17]_2_AG36") (pintype "passive+no_connect"))
    )
    (net (code "152") (name "unconnected-(U2C-TEST_GPIO[18]_2-PadAG35)") (class "Default")
      (node (ref "U2") (pin "AG35") (pinfunction "TEST_GPIO[18]_2_AG35") (pintype "passive+no_connect"))
    )
    (net (code "153") (name "unconnected-(U2C-TEST_GPIO[19]_2-PadAG33)") (class "Default")
      (node (ref "U2") (pin "AG33") (pinfunction "TEST_GPIO[19]_2_AG33") (pintype "passive+no_connect"))
    )
    (net (code "154") (name "unconnected-(U2C-TEST_GPIO[20]_2-PadAG34)") (class "Default")
      (node (ref "U2") (pin "AG34") (pinfunction "TEST_GPIO[20]_2_AG34") (pintype "passive+no_connect"))
    )
    (net (code "155") (name "unconnected-(U2C-TEST_GPIO[21]_2-PadAH36)") (class "Default")
      (node (ref "U2") (pin "AH36") (pinfunction "TEST_GPIO[21]_2_AH36") (pintype "passive+no_connect"))
    )
    (net (code "156") (name "unconnected-(U2C-TEST_GPIO[22]_2-PadAH35)") (class "Default")
      (node (ref "U2") (pin "AH35") (pinfunction "TEST_GPIO[22]_2_AH35") (pintype "passive+no_connect"))
    )
    (net (code "157") (name "unconnected-(U2C-TEST_GPIO[23]_2-PadAJ35)") (class "Default")
      (node (ref "U2") (pin "AJ35") (pinfunction "TEST_GPIO[23]_2_AJ35") (pintype "passive+no_connect"))
    )
    (net (code "158") (name "unconnected-(U2C-TEST_GPIO[24]_2-PadAH33)") (class "Default")
      (node (ref "U2") (pin "AH33") (pinfunction "TEST_GPIO[24]_2_AH33") (pintype "passive+no_connect"))
    )
    (net (code "159") (name "unconnected-(U2C-TEST_GPIO[25]_2-PadAJ34)") (class "Default")
      (node (ref "U2") (pin "AJ34") (pinfunction "TEST_GPIO[25]_2_AJ34") (pintype "passive+no_connect"))
    )
    (net (code "160") (name "unconnected-(U2C-TEST_GPIO[26]_2-PadAJ33)") (class "Default")
      (node (ref "U2") (pin "AJ33") (pinfunction "TEST_GPIO[26]_2_AJ33") (pintype "passive+no_connect"))
    )
    (net (code "161") (name "unconnected-(U2C-TEST_GPIO[27]_2-PadAK35)") (class "Default")
      (node (ref "U2") (pin "AK35") (pinfunction "TEST_GPIO[27]_2_AK35") (pintype "passive+no_connect"))
    )
    (net (code "162") (name "unconnected-(U2C-TEST_GPIO[28]_2-PadAK36)") (class "Default")
      (node (ref "U2") (pin "AK36") (pinfunction "TEST_GPIO[28]_2_AK36") (pintype "passive+no_connect"))
    )
    (net (code "163") (name "unconnected-(U2C-TEST_GPIO[29]_2-PadAK34)") (class "Default")
      (node (ref "U2") (pin "AK34") (pinfunction "TEST_GPIO[29]_2_AK34") (pintype "passive+no_connect"))
    )
    (net (code "164") (name "unconnected-(U2C-TEST_GPIO[30]_2-PadAL36)") (class "Default")
      (node (ref "U2") (pin "AL36") (pinfunction "TEST_GPIO[30]_2_AL36") (pintype "passive+no_connect"))
    )
    (net (code "165") (name "unconnected-(U2C-TEST_GPIO[31]_2-PadAM36)") (class "Default")
      (node (ref "U2") (pin "AM36") (pinfunction "TEST_GPIO[31]_2_AM36") (pintype "passive+no_connect"))
    )
    (net (code "166") (name "unconnected-(U2C-TEST_GPIO[32]_2-PadAL34)") (class "Default")
      (node (ref "U2") (pin "AL34") (pinfunction "TEST_GPIO[32]_2_AL34") (pintype "passive+no_connect"))
    )
    (net (code "167") (name "unconnected-(U2C-TEST_GPIO[33]_2-PadAL33)") (class "Default")
      (node (ref "U2") (pin "AL33") (pinfunction "TEST_GPIO[33]_2_AL33") (pintype "passive+no_connect"))
    )
    (net (code "168") (name "unconnected-(U2C-TEST_GPIO[34]_2-PadAM33)") (class "Default")
      (node (ref "U2") (pin "AM33") (pinfunction "TEST_GPIO[34]_2_AM33") (pintype "passive+no_connect"))
    )
    (net (code "169") (name "unconnected-(U2C-TEST_GPIO[35]_2-PadAN36)") (class "Default")
      (node (ref "U2") (pin "AN36") (pinfunction "TEST_GPIO[35]_2_AN36") (pintype "passive+no_connect"))
    )
    (net (code "170") (name "unconnected-(U2C-TEST_GPIO[36]_2-PadAN35)") (class "Default")
      (node (ref "U2") (pin "AN35") (pinfunction "TEST_GPIO[36]_2_AN35") (pintype "passive+no_connect"))
    )
    (net (code "171") (name "unconnected-(U2C-TEST_GPIO[37]_2-PadAN33)") (class "Default")
      (node (ref "U2") (pin "AN33") (pinfunction "TEST_GPIO[37]_2_AN33") (pintype "passive+no_connect"))
    )
    (net (code "172") (name "unconnected-(U2C-TEST_GPIO[38]_2-PadAP35)") (class "Default")
      (node (ref "U2") (pin "AP35") (pinfunction "TEST_GPIO[38]_2_AP35") (pintype "passive+no_connect"))
    )
    (net (code "173") (name "unconnected-(U2C-TEST_GPIO[39]_2-PadAN32)") (class "Default")
      (node (ref "U2") (pin "AN32") (pinfunction "TEST_GPIO[39]_2_AN32") (pintype "passive+no_connect"))
    )
    (net (code "174") (name "unconnected-(U2C-TEST_GPIO[40]_2-PadAP34)") (class "Default")
      (node (ref "U2") (pin "AP34") (pinfunction "TEST_GPIO[40]_2_AP34") (pintype "passive+no_connect"))
    )
    (net (code "175") (name "unconnected-(U2C-TEST_GPIO[41]_2-PadAP33)") (class "Default")
      (node (ref "U2") (pin "AP33") (pinfunction "TEST_GPIO[41]_2_AP33") (pintype "passive+no_connect"))
    )
    (net (code "176") (name "unconnected-(U2C-TEST_GPIO[42]_2-PadAR35)") (class "Default")
      (node (ref "U2") (pin "AR35") (pinfunction "TEST_GPIO[42]_2_AR35") (pintype "passive+no_connect"))
    )
    (net (code "177") (name "unconnected-(U2C-TEST_GPIO[43]_2-PadAN31)") (class "Default")
      (node (ref "U2") (pin "AN31") (pinfunction "TEST_GPIO[43]_2_AN31") (pintype "passive+no_connect"))
    )
    (net (code "178") (name "unconnected-(U2C-TEST_GPIO[44]_2-PadAP32)") (class "Default")
      (node (ref "U2") (pin "AP32") (pinfunction "TEST_GPIO[44]_2_AP32") (pintype "passive+no_connect"))
    )
    (net (code "179") (name "unconnected-(U2C-TEST_GPIO[45]_2-PadAR34)") (class "Default")
      (node (ref "U2") (pin "AR34") (pinfunction "TEST_GPIO[45]_2_AR34") (pintype "passive+no_connect"))
    )
    (net (code "180") (name "unconnected-(U2C-TEST_GPIO[46]_2-PadAT34)") (class "Default")
      (node (ref "U2") (pin "AT34") (pinfunction "TEST_GPIO[46]_2_AT34") (pintype "passive+no_connect"))
    )
    (net (code "181") (name "unconnected-(U2C-TEST_GPIO[47]_2-PadAN30)") (class "Default")
      (node (ref "U2") (pin "AN30") (pinfunction "TEST_GPIO[47]_2_AN30") (pintype "passive+no_connect"))
    )
    (net (code "182") (name "unconnected-(U2C-TEST_GPIO[48]_2-PadAR32)") (class "Default")
      (node (ref "U2") (pin "AR32") (pinfunction "TEST_GPIO[48]_2_AR32") (pintype "passive+no_connect"))
    )
    (net (code "183") (name "unconnected-(U2C-TEST_GPIO[49]_2-PadAT33)") (class "Default")
      (node (ref "U2") (pin "AT33") (pinfunction "TEST_GPIO[49]_2_AT33") (pintype "passive+no_connect"))
    )
    (net (code "184") (name "unconnected-(U2C-TEST_GPIO[50]_2-PadAP30)") (class "Default")
      (node (ref "U2") (pin "AP30") (pinfunction "TEST_GPIO[50]_2_AP30") (pintype "passive+no_connect"))
    )
    (net (code "185") (name "unconnected-(U2C-TEST_GPIO[51]_2-PadAR31)") (class "Default")
      (node (ref "U2") (pin "AR31") (pinfunction "TEST_GPIO[51]_2_AR31") (pintype "passive+no_connect"))
    )
    (net (code "186") (name "unconnected-(U2C-TEST_GPIO[52]_2-PadAP24)") (class "Default")
      (node (ref "U2") (pin "AP24") (pinfunction "TEST_GPIO[52]_2_AP24") (pintype "passive+no_connect"))
    )
    (net (code "187") (name "unconnected-(U2C-TEST_GPIO[53]_2-PadAR24)") (class "Default")
      (node (ref "U2") (pin "AR24") (pinfunction "TEST_GPIO[53]_2_AR24") (pintype "passive+no_connect"))
    )
    (net (code "188") (name "unconnected-(U2C-TEST_GPIO[54]_2-PadAP23)") (class "Default")
      (node (ref "U2") (pin "AP23") (pinfunction "TEST_GPIO[54]_2_AP23") (pintype "passive+no_connect"))
    )
    (net (code "189") (name "unconnected-(U2C-TEST_GPIO[55]_2-PadAN23)") (class "Default")
      (node (ref "U2") (pin "AN23") (pinfunction "TEST_GPIO[55]_2_AN23") (pintype "passive+no_connect"))
    )
    (net (code "190") (name "unconnected-(U2C-TEST_GPIO[56]_2-PadAT24)") (class "Default")
      (node (ref "U2") (pin "AT24") (pinfunction "TEST_GPIO[56]_2_AT24") (pintype "passive+no_connect"))
    )
    (net (code "191") (name "unconnected-(U2C-TEST_GPIO[57]_2-PadAT23)") (class "Default")
      (node (ref "U2") (pin "AT23") (pinfunction "TEST_GPIO[57]_2_AT23") (pintype "passive+no_connect"))
    )
    (net (code "192") (name "unconnected-(U2C-TEST_GPIO[58]_2-PadAP22)") (class "Default")
      (node (ref "U2") (pin "AP22") (pinfunction "TEST_GPIO[58]_2_AP22") (pintype "passive+no_connect"))
    )
    (net (code "193") (name "unconnected-(U2C-TEST_GPIO[59]_2-PadAN22)") (class "Default")
      (node (ref "U2") (pin "AN22") (pinfunction "TEST_GPIO[59]_2_AN22") (pintype "passive+no_connect"))
    )
    (net (code "194") (name "unconnected-(U2C-TEST_GPIO[60]_2-PadAR22)") (class "Default")
      (node (ref "U2") (pin "AR22") (pinfunction "TEST_GPIO[60]_2_AR22") (pintype "passive+no_connect"))
    )
    (net (code "195") (name "unconnected-(U2C-TEST_GPIO[61]_2-PadAT21)") (class "Default")
      (node (ref "U2") (pin "AT21") (pinfunction "TEST_GPIO[61]_2_AT21") (pintype "passive+no_connect"))
    )
    (net (code "196") (name "unconnected-(U2C-TEST_GPIO[62]_2-PadAT22)") (class "Default")
      (node (ref "U2") (pin "AT22") (pinfunction "TEST_GPIO[62]_2_AT22") (pintype "passive+no_connect"))
    )
    (net (code "197") (name "unconnected-(U2C-TEST_GPIO[63]_2-PadAR21)") (class "Default")
      (node (ref "U2") (pin "AR21") (pinfunction "TEST_GPIO[63]_2_AR21") (pintype "passive+no_connect"))
    )
    (net (code "198") (name "unconnected-(U2C-TEST_GPIO[64]_2-PadAN21)") (class "Default")
      (node (ref "U2") (pin "AN21") (pinfunction "TEST_GPIO[64]_2_AN21") (pintype "passive+no_connect"))
    )
    (net (code "199") (name "unconnected-(U2C-TEST_GPIO[65]_2-PadAP20)") (class "Default")
      (node (ref "U2") (pin "AP20") (pinfunction "TEST_GPIO[65]_2_AP20") (pintype "passive+no_connect"))
    )
    (net (code "200") (name "unconnected-(U2C-TEST_GPIO[66]_2-PadAR20)") (class "Default")
      (node (ref "U2") (pin "AR20") (pinfunction "TEST_GPIO[66]_2_AR20") (pintype "passive+no_connect"))
    )
    (net (code "201") (name "unconnected-(U2C-TEST_GPIO[67]_2-PadAN20)") (class "Default")
      (node (ref "U2") (pin "AN20") (pinfunction "TEST_GPIO[67]_2_AN20") (pintype "passive+no_connect"))
    )
    (net (code "202") (name "unconnected-(U2C-TEST_GPIO[68]_2-PadAT19)") (class "Default")
      (node (ref "U2") (pin "AT19") (pinfunction "TEST_GPIO[68]_2_AT19") (pintype "passive+no_connect"))
    )
    (net (code "203") (name "unconnected-(U2C-TEST_GPIO[69]_2-PadAP19)") (class "Default")
      (node (ref "U2") (pin "AP19") (pinfunction "TEST_GPIO[69]_2_AP19") (pintype "passive+no_connect"))
    )
    (net (code "204") (name "unconnected-(U2C-TEST_GPIO[70]_2-PadAR19)") (class "Default")
      (node (ref "U2") (pin "AR19") (pinfunction "TEST_GPIO[70]_2_AR19") (pintype "passive+no_connect"))
    )
    (net (code "205") (name "unconnected-(U2C-TEST_GPIO[71]_2-PadAM19)") (class "Default")
      (node (ref "U2") (pin "AM19") (pinfunction "TEST_GPIO[71]_2_AM19") (pintype "passive+no_connect"))
    )
    (net (code "206") (name "unconnected-(U2D-DBG_SPARE[0]_3-PadM34)") (class "Default")
      (node (ref "U2") (pin "M34") (pinfunction "DBG_SPARE[0]_3_M34") (pintype "passive+no_connect"))
    )
    (net (code "207") (name "unconnected-(U2D-DBG_SPARE[1]_3-PadM35)") (class "Default")
      (node (ref "U2") (pin "M35") (pinfunction "DBG_SPARE[1]_3_M35") (pintype "passive+no_connect"))
    )
    (net (code "208") (name "unconnected-(U2D-JTG_TCK_3-PadD26)") (class "Default")
      (node (ref "U2") (pin "D26") (pinfunction "JTG_TCK_3_D26") (pintype "passive+no_connect"))
    )
    (net (code "209") (name "unconnected-(U2D-JTG_TDI_3-PadA26)") (class "Default")
      (node (ref "U2") (pin "A26") (pinfunction "JTG_TDI_3_A26") (pintype "passive+no_connect"))
    )
    (net (code "210") (name "unconnected-(U2D-JTG_TDO_3-PadC25)") (class "Default")
      (node (ref "U2") (pin "C25") (pinfunction "JTG_TDO_3_C25") (pintype "passive+no_connect"))
    )
    (net (code "211") (name "unconnected-(U2D-JTG_TMS_3-PadA25)") (class "Default")
      (node (ref "U2") (pin "A25") (pinfunction "JTG_TMS_3_A25") (pintype "passive+no_connect"))
    )
    (net (code "212") (name "unconnected-(U2D-TEST_GPIO[0]_3-PadB19)") (class "Default")
      (node (ref "U2") (pin "B19") (pinfunction "TEST_GPIO[0]_3_B19") (pintype "passive+no_connect"))
    )
    (net (code "213") (name "unconnected-(U2D-TEST_GPIO[1]_3-PadB20)") (class "Default")
      (node (ref "U2") (pin "B20") (pinfunction "TEST_GPIO[1]_3_B20") (pintype "passive+no_connect"))
    )
    (net (code "214") (name "unconnected-(U2D-TEST_GPIO[2]_3-PadC20)") (class "Default")
      (node (ref "U2") (pin "C20") (pinfunction "TEST_GPIO[2]_3_C20") (pintype "passive+no_connect"))
    )
    (net (code "215") (name "unconnected-(U2D-TEST_GPIO[3]_3-PadA20)") (class "Default")
      (node (ref "U2") (pin "A20") (pinfunction "TEST_GPIO[3]_3_A20") (pintype "passive+no_connect"))
    )
    (net (code "216") (name "unconnected-(U2D-TEST_GPIO[4]_3-PadD21)") (class "Default")
      (node (ref "U2") (pin "D21") (pinfunction "TEST_GPIO[4]_3_D21") (pintype "passive+no_connect"))
    )
    (net (code "217") (name "unconnected-(U2D-TEST_GPIO[5]_3-PadA21)") (class "Default")
      (node (ref "U2") (pin "A21") (pinfunction "TEST_GPIO[5]_3_A21") (pintype "passive+no_connect"))
    )
    (net (code "218") (name "unconnected-(U2D-TEST_GPIO[6]_3-PadC21)") (class "Default")
      (node (ref "U2") (pin "C21") (pinfunction "TEST_GPIO[6]_3_C21") (pintype "passive+no_connect"))
    )
    (net (code "219") (name "unconnected-(U2D-TEST_GPIO[7]_3-PadD22)") (class "Default")
      (node (ref "U2") (pin "D22") (pinfunction "TEST_GPIO[7]_3_D22") (pintype "passive+no_connect"))
    )
    (net (code "220") (name "unconnected-(U2D-TEST_GPIO[8]_3-PadC22)") (class "Default")
      (node (ref "U2") (pin "C22") (pinfunction "TEST_GPIO[8]_3_C22") (pintype "passive+no_connect"))
    )
    (net (code "221") (name "unconnected-(U2D-TEST_GPIO[9]_3-PadA22)") (class "Default")
      (node (ref "U2") (pin "A22") (pinfunction "TEST_GPIO[9]_3_A22") (pintype "passive+no_connect"))
    )
    (net (code "222") (name "unconnected-(U2D-TEST_GPIO[10]_3-PadB22)") (class "Default")
      (node (ref "U2") (pin "B22") (pinfunction "TEST_GPIO[10]_3_B22") (pintype "passive+no_connect"))
    )
    (net (code "223") (name "unconnected-(U2D-TEST_GPIO[11]_3-PadD23)") (class "Default")
      (node (ref "U2") (pin "D23") (pinfunction "TEST_GPIO[11]_3_D23") (pintype "passive+no_connect"))
    )
    (net (code "224") (name "unconnected-(U2D-TEST_GPIO[12]_3-PadB23)") (class "Default")
      (node (ref "U2") (pin "B23") (pinfunction "TEST_GPIO[12]_3_B23") (pintype "passive+no_connect"))
    )
    (net (code "225") (name "unconnected-(U2D-TEST_GPIO[13]_3-PadB24)") (class "Default")
      (node (ref "U2") (pin "B24") (pinfunction "TEST_GPIO[13]_3_B24") (pintype "passive+no_connect"))
    )
    (net (code "226") (name "unconnected-(U2D-TEST_GPIO[14]_3-PadA23)") (class "Default")
      (node (ref "U2") (pin "A23") (pinfunction "TEST_GPIO[14]_3_A23") (pintype "passive+no_connect"))
    )
    (net (code "227") (name "unconnected-(U2D-TEST_GPIO[15]_3-PadC24)") (class "Default")
      (node (ref "U2") (pin "C24") (pinfunction "TEST_GPIO[15]_3_C24") (pintype "passive+no_connect"))
    )
    (net (code "228") (name "unconnected-(U2D-TEST_GPIO[16]_3-PadC26)") (class "Default")
      (node (ref "U2") (pin "C26") (pinfunction "TEST_GPIO[16]_3_C26") (pintype "passive+no_connect"))
    )
    (net (code "229") (name "unconnected-(U2D-TEST_GPIO[17]_3-PadA27)") (class "Default")
      (node (ref "U2") (pin "A27") (pinfunction "TEST_GPIO[17]_3_A27") (pintype "passive+no_connect"))
    )
    (net (code "230") (name "unconnected-(U2D-TEST_GPIO[18]_3-PadB27)") (class "Default")
      (node (ref "U2") (pin "B27") (pinfunction "TEST_GPIO[18]_3_B27") (pintype "passive+no_connect"))
    )
    (net (code "231") (name "unconnected-(U2D-TEST_GPIO[19]_3-PadD27)") (class "Default")
      (node (ref "U2") (pin "D27") (pinfunction "TEST_GPIO[19]_3_D27") (pintype "passive+no_connect"))
    )
    (net (code "232") (name "unconnected-(U2D-TEST_GPIO[20]_3-PadC27)") (class "Default")
      (node (ref "U2") (pin "C27") (pinfunction "TEST_GPIO[20]_3_C27") (pintype "passive+no_connect"))
    )
    (net (code "233") (name "unconnected-(U2D-TEST_GPIO[21]_3-PadA28)") (class "Default")
      (node (ref "U2") (pin "A28") (pinfunction "TEST_GPIO[21]_3_A28") (pintype "passive+no_connect"))
    )
    (net (code "234") (name "unconnected-(U2D-TEST_GPIO[22]_3-PadB28)") (class "Default")
      (node (ref "U2") (pin "B28") (pinfunction "TEST_GPIO[22]_3_B28") (pintype "passive+no_connect"))
    )
    (net (code "235") (name "unconnected-(U2D-TEST_GPIO[23]_3-PadB29)") (class "Default")
      (node (ref "U2") (pin "B29") (pinfunction "TEST_GPIO[23]_3_B29") (pintype "passive+no_connect"))
    )
    (net (code "236") (name "unconnected-(U2D-TEST_GPIO[24]_3-PadD28)") (class "Default")
      (node (ref "U2") (pin "D28") (pinfunction "TEST_GPIO[24]_3_D28") (pintype "passive+no_connect"))
    )
    (net (code "237") (name "unconnected-(U2D-TEST_GPIO[25]_3-PadC29)") (class "Default")
      (node (ref "U2") (pin "C29") (pinfunction "TEST_GPIO[25]_3_C29") (pintype "passive+no_connect"))
    )
    (net (code "238") (name "unconnected-(U2D-TEST_GPIO[26]_3-PadD29)") (class "Default")
      (node (ref "U2") (pin "D29") (pinfunction "TEST_GPIO[26]_3_D29") (pintype "passive+no_connect"))
    )
    (net (code "239") (name "unconnected-(U2D-TEST_GPIO[27]_3-PadB30)") (class "Default")
      (node (ref "U2") (pin "B30") (pinfunction "TEST_GPIO[27]_3_B30") (pintype "passive+no_connect"))
    )
    (net (code "240") (name "unconnected-(U2D-TEST_GPIO[28]_3-PadA30)") (class "Default")
      (node (ref "U2") (pin "A30") (pinfunction "TEST_GPIO[28]_3_A30") (pintype "passive+no_connect"))
    )
    (net (code "241") (name "unconnected-(U2D-TEST_GPIO[29]_3-PadC30)") (class "Default")
      (node (ref "U2") (pin "C30") (pinfunction "TEST_GPIO[29]_3_C30") (pintype "passive+no_connect"))
    )
    (net (code "242") (name "unconnected-(U2D-TEST_GPIO[30]_3-PadA31)") (class "Default")
      (node (ref "U2") (pin "A31") (pinfunction "TEST_GPIO[30]_3_A31") (pintype "passive+no_connect"))
    )
    (net (code "243") (name "unconnected-(U2D-TEST_GPIO[31]_3-PadA32)") (class "Default")
      (node (ref "U2") (pin "A32") (pinfunction "TEST_GPIO[31]_3_A32") (pintype "passive+no_connect"))
    )
    (net (code "244") (name "unconnected-(U2D-TEST_GPIO[32]_3-PadC31)") (class "Default")
      (node (ref "U2") (pin "C31") (pinfunction "TEST_GPIO[32]_3_C31") (pintype "passive+no_connect"))
    )
    (net (code "245") (name "unconnected-(U2D-TEST_GPIO[33]_3-PadD31)") (class "Default")
      (node (ref "U2") (pin "D31") (pinfunction "TEST_GPIO[33]_3_D31") (pintype "passive+no_connect"))
    )
    (net (code "246") (name "unconnected-(U2D-TEST_GPIO[34]_3-PadD32)") (class "Default")
      (node (ref "U2") (pin "D32") (pinfunction "TEST_GPIO[34]_3_D32") (pintype "passive+no_connect"))
    )
    (net (code "247") (name "unconnected-(U2D-TEST_GPIO[35]_3-PadA33)") (class "Default")
      (node (ref "U2") (pin "A33") (pinfunction "TEST_GPIO[35]_3_A33") (pintype "passive+no_connect"))
    )
    (net (code "248") (name "unconnected-(U2D-TEST_GPIO[36]_3-PadB33)") (class "Default")
      (node (ref "U2") (pin "B33") (pinfunction "TEST_GPIO[36]_3_B33") (pintype "passive+no_connect"))
    )
    (net (code "249") (name "unconnected-(U2D-TEST_GPIO[37]_3-PadD33)") (class "Default")
      (node (ref "U2") (pin "D33") (pinfunction "TEST_GPIO[37]_3_D33") (pintype "passive+no_connect"))
    )
    (net (code "250") (name "unconnected-(U2D-TEST_GPIO[38]_3-PadB34)") (class "Default")
      (node (ref "U2") (pin "B34") (pinfunction "TEST_GPIO[38]_3_B34") (pintype "passive+no_connect"))
    )
    (net (code "251") (name "unconnected-(U2D-TEST_GPIO[39]_3-PadE33)") (class "Default")
      (node (ref "U2") (pin "E33") (pinfunction "TEST_GPIO[39]_3_E33") (pintype "passive+no_connect"))
    )
    (net (code "252") (name "unconnected-(U2D-TEST_GPIO[40]_3-PadC34)") (class "Default")
      (node (ref "U2") (pin "C34") (pinfunction "TEST_GPIO[40]_3_C34") (pintype "passive+no_connect"))
    )
    (net (code "253") (name "unconnected-(U2D-TEST_GPIO[41]_3-PadD34)") (class "Default")
      (node (ref "U2") (pin "D34") (pinfunction "TEST_GPIO[41]_3_D34") (pintype "passive+no_connect"))
    )
    (net (code "254") (name "unconnected-(U2D-TEST_GPIO[42]_3-PadB35)") (class "Default")
      (node (ref "U2") (pin "B35") (pinfunction "TEST_GPIO[42]_3_B35") (pintype "passive+no_connect"))
    )
    (net (code "255") (name "unconnected-(U2D-TEST_GPIO[43]_3-PadF33)") (class "Default")
      (node (ref "U2") (pin "F33") (pinfunction "TEST_GPIO[43]_3_F33") (pintype "passive+no_connect"))
    )
    (net (code "256") (name "unconnected-(U2D-TEST_GPIO[44]_3-PadE34)") (class "Default")
      (node (ref "U2") (pin "E34") (pinfunction "TEST_GPIO[44]_3_E34") (pintype "passive+no_connect"))
    )
    (net (code "257") (name "unconnected-(U2D-TEST_GPIO[45]_3-PadC35)") (class "Default")
      (node (ref "U2") (pin "C35") (pinfunction "TEST_GPIO[45]_3_C35") (pintype "passive+no_connect"))
    )
    (net (code "258") (name "unconnected-(U2D-TEST_GPIO[46]_3-PadC36)") (class "Default")
      (node (ref "U2") (pin "C36") (pinfunction "TEST_GPIO[46]_3_C36") (pintype "passive+no_connect"))
    )
    (net (code "259") (name "unconnected-(U2D-TEST_GPIO[47]_3-PadG33)") (class "Default")
      (node (ref "U2") (pin "G33") (pinfunction "TEST_GPIO[47]_3_G33") (pintype "passive+no_connect"))
    )
    (net (code "260") (name "unconnected-(U2D-TEST_GPIO[48]_3-PadE35)") (class "Default")
      (node (ref "U2") (pin "E35") (pinfunction "TEST_GPIO[48]_3_E35") (pintype "passive+no_connect"))
    )
    (net (code "261") (name "unconnected-(U2D-TEST_GPIO[49]_3-PadD36)") (class "Default")
      (node (ref "U2") (pin "D36") (pinfunction "TEST_GPIO[49]_3_D36") (pintype "passive+no_connect"))
    )
    (net (code "262") (name "unconnected-(U2D-TEST_GPIO[50]_3-PadG34)") (class "Default")
      (node (ref "U2") (pin "G34") (pinfunction "TEST_GPIO[50]_3_G34") (pintype "passive+no_connect"))
    )
    (net (code "263") (name "unconnected-(U2D-TEST_GPIO[51]_3-PadF35)") (class "Default")
      (node (ref "U2") (pin "F35") (pinfunction "TEST_GPIO[51]_3_F35") (pintype "passive+no_connect"))
    )
    (net (code "264") (name "unconnected-(U2D-TEST_GPIO[52]_3-PadN34)") (class "Default")
      (node (ref "U2") (pin "N34") (pinfunction "TEST_GPIO[52]_3_N34") (pintype "passive+no_connect"))
    )
    (net (code "265") (name "unconnected-(U2D-TEST_GPIO[53]_3-PadN35)") (class "Default")
      (node (ref "U2") (pin "N35") (pinfunction "TEST_GPIO[53]_3_N35") (pintype "passive+no_connect"))
    )
    (net (code "266") (name "unconnected-(U2D-TEST_GPIO[54]_3-PadP34)") (class "Default")
      (node (ref "U2") (pin "P34") (pinfunction "TEST_GPIO[54]_3_P34") (pintype "passive+no_connect"))
    )
    (net (code "267") (name "unconnected-(U2D-TEST_GPIO[55]_3-PadP33)") (class "Default")
      (node (ref "U2") (pin "P33") (pinfunction "TEST_GPIO[55]_3_P33") (pintype "passive+no_connect"))
    )
    (net (code "268") (name "unconnected-(U2D-TEST_GPIO[56]_3-PadN36)") (class "Default")
      (node (ref "U2") (pin "N36") (pinfunction "TEST_GPIO[56]_3_N36") (pintype "passive+no_connect"))
    )
    (net (code "269") (name "unconnected-(U2D-TEST_GPIO[57]_3-PadP36)") (class "Default")
      (node (ref "U2") (pin "P36") (pinfunction "TEST_GPIO[57]_3_P36") (pintype "passive+no_connect"))
    )
    (net (code "270") (name "unconnected-(U2D-TEST_GPIO[58]_3-PadR34)") (class "Default")
      (node (ref "U2") (pin "R34") (pinfunction "TEST_GPIO[58]_3_R34") (pintype "passive+no_connect"))
    )
    (net (code "271") (name "unconnected-(U2D-TEST_GPIO[59]_3-PadR33)") (class "Default")
      (node (ref "U2") (pin "R33") (pinfunction "TEST_GPIO[59]_3_R33") (pintype "passive+no_connect"))
    )
    (net (code "272") (name "unconnected-(U2D-TEST_GPIO[60]_3-PadR35)") (class "Default")
      (node (ref "U2") (pin "R35") (pinfunction "TEST_GPIO[60]_3_R35") (pintype "passive+no_connect"))
    )
    (net (code "273") (name "unconnected-(U2D-TEST_GPIO[61]_3-PadT36)") (class "Default")
      (node (ref "U2") (pin "T36") (pinfunction "TEST_GPIO[61]_3_T36") (pintype "passive+no_connect"))
    )
    (net (code "274") (name "unconnected-(U2D-TEST_GPIO[62]_3-PadR36)") (class "Default")
      (node (ref "U2") (pin "R36") (pinfunction "TEST_GPIO[62]_3_R36") (pintype "passive+no_connect"))
    )
    (net (code "275") (name "unconnected-(U2D-TEST_GPIO[63]_3-PadT35)") (class "Default")
      (node (ref "U2") (pin "T35") (pinfunction "TEST_GPIO[63]_3_T35") (pintype "passive+no_connect"))
    )
    (net (code "276") (name "unconnected-(U2D-TEST_GPIO[64]_3-PadT33)") (class "Default")
      (node (ref "U2") (pin "T33") (pinfunction "TEST_GPIO[64]_3_T33") (pintype "passive+no_connect"))
    )
    (net (code "277") (name "unconnected-(U2D-TEST_GPIO[65]_3-PadU34)") (class "Default")
      (node (ref "U2") (pin "U34") (pinfunction "TEST_GPIO[65]_3_U34") (pintype "passive+no_connect"))
    )
    (net (code "278") (name "unconnected-(U2D-TEST_GPIO[66]_3-PadU35)") (class "Default")
      (node (ref "U2") (pin "U35") (pinfunction "TEST_GPIO[66]_3_U35") (pintype "passive+no_connect"))
    )
    (net (code "279") (name "unconnected-(U2D-TEST_GPIO[67]_3-PadU33)") (class "Default")
      (node (ref "U2") (pin "U33") (pinfunction "TEST_GPIO[67]_3_U33") (pintype "passive+no_connect"))
    )
    (net (code "280") (name "unconnected-(U2D-TEST_GPIO[68]_3-PadV36)") (class "Default")
      (node (ref "U2") (pin "V36") (pinfunction "TEST_GPIO[68]_3_V36") (pintype "passive+no_connect"))
    )
    (net (code "281") (name "unconnected-(U2D-TEST_GPIO[69]_3-PadV34)") (class "Default")
      (node (ref "U2") (pin "V34") (pinfunction "TEST_GPIO[69]_3_V34") (pintype "passive+no_connect"))
    )
    (net (code "282") (name "unconnected-(U2D-TEST_GPIO[70]_3-PadV35)") (class "Default")
      (node (ref "U2") (pin "V35") (pinfunction "TEST_GPIO[70]_3_V35") (pintype "passive+no_connect"))
    )
    (net (code "283") (name "unconnected-(U2D-TEST_GPIO[71]_3-PadV32)") (class "Default")
      (node (ref "U2") (pin "V32") (pinfunction "TEST_GPIO[71]_3_V32") (pintype "passive+no_connect"))
    )
    (net (code "284") (name "unconnected-(U2E-DBG_SPARE[0]_4-PadC12)") (class "Default")
      (node (ref "U2") (pin "C12") (pinfunction "DBG_SPARE[0]_4_C12") (pintype "passive+no_connect"))
    )
    (net (code "285") (name "unconnected-(U2E-DBG_SPARE[1]_4-PadB12)") (class "Default")
      (node (ref "U2") (pin "B12") (pinfunction "DBG_SPARE[1]_4_B12") (pintype "passive+no_connect"))
    )
    (net (code "286") (name "unconnected-(U2E-JTG_TCK_4-PadL4)") (class "Default")
      (node (ref "U2") (pin "L4") (pinfunction "JTG_TCK_4_L4") (pintype "passive+no_connect"))
    )
    (net (code "287") (name "unconnected-(U2E-JTG_TDI_4-PadL1)") (class "Default")
      (node (ref "U2") (pin "L1") (pinfunction "JTG_TDI_4_L1") (pintype "passive+no_connect"))
    )
    (net (code "288") (name "unconnected-(U2E-JTG_TDO_4-PadM3)") (class "Default")
      (node (ref "U2") (pin "M3") (pinfunction "JTG_TDO_4_M3") (pintype "passive+no_connect"))
    )
    (net (code "289") (name "unconnected-(U2E-JTG_TMS_4-PadM1)") (class "Default")
      (node (ref "U2") (pin "M1") (pinfunction "JTG_TMS_4_M1") (pintype "passive+no_connect"))
    )
    (net (code "290") (name "unconnected-(U2E-TEST_GPIO[0]_4-PadV2)") (class "Default")
      (node (ref "U2") (pin "V2") (pinfunction "TEST_GPIO[0]_4_V2") (pintype "passive+no_connect"))
    )
    (net (code "291") (name "unconnected-(U2E-TEST_GPIO[1]_4-PadU2)") (class "Default")
      (node (ref "U2") (pin "U2") (pinfunction "TEST_GPIO[1]_4_U2") (pintype "passive+no_connect"))
    )
    (net (code "292") (name "unconnected-(U2E-TEST_GPIO[2]_4-PadU3)") (class "Default")
      (node (ref "U2") (pin "U3") (pinfunction "TEST_GPIO[2]_4_U3") (pintype "passive+no_connect"))
    )
    (net (code "293") (name "unconnected-(U2E-TEST_GPIO[3]_4-PadU1)") (class "Default")
      (node (ref "U2") (pin "U1") (pinfunction "TEST_GPIO[3]_4_U1") (pintype "passive+no_connect"))
    )
    (net (code "294") (name "unconnected-(U2E-TEST_GPIO[4]_4-PadT4)") (class "Default")
      (node (ref "U2") (pin "T4") (pinfunction "TEST_GPIO[4]_4_T4") (pintype "passive+no_connect"))
    )
    (net (code "295") (name "unconnected-(U2E-TEST_GPIO[5]_4-PadT1)") (class "Default")
      (node (ref "U2") (pin "T1") (pinfunction "TEST_GPIO[5]_4_T1") (pintype "passive+no_connect"))
    )
    (net (code "296") (name "unconnected-(U2E-TEST_GPIO[6]_4-PadT3)") (class "Default")
      (node (ref "U2") (pin "T3") (pinfunction "TEST_GPIO[6]_4_T3") (pintype "passive+no_connect"))
    )
    (net (code "297") (name "unconnected-(U2E-TEST_GPIO[7]_4-PadR4)") (class "Default")
      (node (ref "U2") (pin "R4") (pinfunction "TEST_GPIO[7]_4_R4") (pintype "passive+no_connect"))
    )
    (net (code "298") (name "unconnected-(U2E-TEST_GPIO[8]_4-PadR3)") (class "Default")
      (node (ref "U2") (pin "R3") (pinfunction "TEST_GPIO[8]_4_R3") (pintype "passive+no_connect"))
    )
    (net (code "299") (name "unconnected-(U2E-TEST_GPIO[9]_4-PadR1)") (class "Default")
      (node (ref "U2") (pin "R1") (pinfunction "TEST_GPIO[9]_4_R1") (pintype "passive+no_connect"))
    )
    (net (code "300") (name "unconnected-(U2E-TEST_GPIO[10]_4-PadR2)") (class "Default")
      (node (ref "U2") (pin "R2") (pinfunction "TEST_GPIO[10]_4_R2") (pintype "passive+no_connect"))
    )
    (net (code "301") (name "unconnected-(U2E-TEST_GPIO[11]_4-PadP4)") (class "Default")
      (node (ref "U2") (pin "P4") (pinfunction "TEST_GPIO[11]_4_P4") (pintype "passive+no_connect"))
    )
    (net (code "302") (name "unconnected-(U2E-TEST_GPIO[12]_4-PadP2)") (class "Default")
      (node (ref "U2") (pin "P2") (pinfunction "TEST_GPIO[12]_4_P2") (pintype "passive+no_connect"))
    )
    (net (code "303") (name "unconnected-(U2E-TEST_GPIO[13]_4-PadN2)") (class "Default")
      (node (ref "U2") (pin "N2") (pinfunction "TEST_GPIO[13]_4_N2") (pintype "passive+no_connect"))
    )
    (net (code "304") (name "unconnected-(U2E-TEST_GPIO[14]_4-PadP1)") (class "Default")
      (node (ref "U2") (pin "P1") (pinfunction "TEST_GPIO[14]_4_P1") (pintype "passive+no_connect"))
    )
    (net (code "305") (name "unconnected-(U2E-TEST_GPIO[15]_4-PadN3)") (class "Default")
      (node (ref "U2") (pin "N3") (pinfunction "TEST_GPIO[15]_4_N3") (pintype "passive+no_connect"))
    )
    (net (code "306") (name "unconnected-(U2E-TEST_GPIO[16]_4-PadL3)") (class "Default")
      (node (ref "U2") (pin "L3") (pinfunction "TEST_GPIO[16]_4_L3") (pintype "passive+no_connect"))
    )
    (net (code "307") (name "unconnected-(U2E-TEST_GPIO[17]_4-PadK1)") (class "Default")
      (node (ref "U2") (pin "K1") (pinfunction "TEST_GPIO[17]_4_K1") (pintype "passive+no_connect"))
    )
    (net (code "308") (name "unconnected-(U2E-TEST_GPIO[18]_4-PadK2)") (class "Default")
      (node (ref "U2") (pin "K2") (pinfunction "TEST_GPIO[18]_4_K2") (pintype "passive+no_connect"))
    )
    (net (code "309") (name "unconnected-(U2E-TEST_GPIO[19]_4-PadK4)") (class "Default")
      (node (ref "U2") (pin "K4") (pinfunction "TEST_GPIO[19]_4_K4") (pintype "passive+no_connect"))
    )
    (net (code "310") (name "unconnected-(U2E-TEST_GPIO[20]_4-PadK3)") (class "Default")
      (node (ref "U2") (pin "K3") (pinfunction "TEST_GPIO[20]_4_K3") (pintype "passive+no_connect"))
    )
    (net (code "311") (name "unconnected-(U2E-TEST_GPIO[21]_4-PadJ1)") (class "Default")
      (node (ref "U2") (pin "J1") (pinfunction "TEST_GPIO[21]_4_J1") (pintype "passive+no_connect"))
    )
    (net (code "312") (name "unconnected-(U2E-TEST_GPIO[22]_4-PadJ2)") (class "Default")
      (node (ref "U2") (pin "J2") (pinfunction "TEST_GPIO[22]_4_J2") (pintype "passive+no_connect"))
    )
    (net (code "313") (name "unconnected-(U2E-TEST_GPIO[23]_4-PadH2)") (class "Default")
      (node (ref "U2") (pin "H2") (pinfunction "TEST_GPIO[23]_4_H2") (pintype "passive+no_connect"))
    )
    (net (code "314") (name "unconnected-(U2E-TEST_GPIO[24]_4-PadJ4)") (class "Default")
      (node (ref "U2") (pin "J4") (pinfunction "TEST_GPIO[24]_4_J4") (pintype "passive+no_connect"))
    )
    (net (code "315") (name "unconnected-(U2E-TEST_GPIO[25]_4-PadH3)") (class "Default")
      (node (ref "U2") (pin "H3") (pinfunction "TEST_GPIO[25]_4_H3") (pintype "passive+no_connect"))
    )
    (net (code "316") (name "unconnected-(U2E-TEST_GPIO[26]_4-PadH4)") (class "Default")
      (node (ref "U2") (pin "H4") (pinfunction "TEST_GPIO[26]_4_H4") (pintype "passive+no_connect"))
    )
    (net (code "317") (name "unconnected-(U2E-TEST_GPIO[27]_4-PadG2)") (class "Default")
      (node (ref "U2") (pin "G2") (pinfunction "TEST_GPIO[27]_4_G2") (pintype "passive+no_connect"))
    )
    (net (code "318") (name "unconnected-(U2E-TEST_GPIO[28]_4-PadG1)") (class "Default")
      (node (ref "U2") (pin "G1") (pinfunction "TEST_GPIO[28]_4_G1") (pintype "passive+no_connect"))
    )
    (net (code "319") (name "unconnected-(U2E-TEST_GPIO[29]_4-PadG3)") (class "Default")
      (node (ref "U2") (pin "G3") (pinfunction "TEST_GPIO[29]_4_G3") (pintype "passive+no_connect"))
    )
    (net (code "320") (name "unconnected-(U2E-TEST_GPIO[30]_4-PadF1)") (class "Default")
      (node (ref "U2") (pin "F1") (pinfunction "TEST_GPIO[30]_4_F1") (pintype "passive+no_connect"))
    )
    (net (code "321") (name "unconnected-(U2E-TEST_GPIO[31]_4-PadE1)") (class "Default")
      (node (ref "U2") (pin "E1") (pinfunction "TEST_GPIO[31]_4_E1") (pintype "passive+no_connect"))
    )
    (net (code "322") (name "unconnected-(U2E-TEST_GPIO[32]_4-PadF3)") (class "Default")
      (node (ref "U2") (pin "F3") (pinfunction "TEST_GPIO[32]_4_F3") (pintype "passive+no_connect"))
    )
    (net (code "323") (name "unconnected-(U2E-TEST_GPIO[33]_4-PadF4)") (class "Default")
      (node (ref "U2") (pin "F4") (pinfunction "TEST_GPIO[33]_4_F4") (pintype "passive+no_connect"))
    )
    (net (code "324") (name "unconnected-(U2E-TEST_GPIO[34]_4-PadE4)") (class "Default")
      (node (ref "U2") (pin "E4") (pinfunction "TEST_GPIO[34]_4_E4") (pintype "passive+no_connect"))
    )
    (net (code "325") (name "unconnected-(U2E-TEST_GPIO[35]_4-PadD1)") (class "Default")
      (node (ref "U2") (pin "D1") (pinfunction "TEST_GPIO[35]_4_D1") (pintype "passive+no_connect"))
    )
    (net (code "326") (name "unconnected-(U2E-TEST_GPIO[36]_4-PadD2)") (class "Default")
      (node (ref "U2") (pin "D2") (pinfunction "TEST_GPIO[36]_4_D2") (pintype "passive+no_connect"))
    )
    (net (code "327") (name "unconnected-(U2E-TEST_GPIO[37]_4-PadD4)") (class "Default")
      (node (ref "U2") (pin "D4") (pinfunction "TEST_GPIO[37]_4_D4") (pintype "passive+no_connect"))
    )
    (net (code "328") (name "unconnected-(U2E-TEST_GPIO[38]_4-PadC2)") (class "Default")
      (node (ref "U2") (pin "C2") (pinfunction "TEST_GPIO[38]_4_C2") (pintype "passive+no_connect"))
    )
    (net (code "329") (name "unconnected-(U2E-TEST_GPIO[39]_4-PadD5)") (class "Default")
      (node (ref "U2") (pin "D5") (pinfunction "TEST_GPIO[39]_4_D5") (pintype "passive+no_connect"))
    )
    (net (code "330") (name "unconnected-(U2E-TEST_GPIO[40]_4-PadC3)") (class "Default")
      (node (ref "U2") (pin "C3") (pinfunction "TEST_GPIO[40]_4_C3") (pintype "passive+no_connect"))
    )
    (net (code "331") (name "unconnected-(U2E-TEST_GPIO[41]_4-PadC4)") (class "Default")
      (node (ref "U2") (pin "C4") (pinfunction "TEST_GPIO[41]_4_C4") (pintype "passive+no_connect"))
    )
    (net (code "332") (name "unconnected-(U2E-TEST_GPIO[42]_4-PadB2)") (class "Default")
      (node (ref "U2") (pin "B2") (pinfunction "TEST_GPIO[42]_4_B2") (pintype "passive+no_connect"))
    )
    (net (code "333") (name "unconnected-(U2E-TEST_GPIO[43]_4-PadD6)") (class "Default")
      (node (ref "U2") (pin "D6") (pinfunction "TEST_GPIO[43]_4_D6") (pintype "passive+no_connect"))
    )
    (net (code "334") (name "unconnected-(U2E-TEST_GPIO[44]_4-PadC5)") (class "Default")
      (node (ref "U2") (pin "C5") (pinfunction "TEST_GPIO[44]_4_C5") (pintype "passive+no_connect"))
    )
    (net (code "335") (name "unconnected-(U2E-TEST_GPIO[45]_4-PadB3)") (class "Default")
      (node (ref "U2") (pin "B3") (pinfunction "TEST_GPIO[45]_4_B3") (pintype "passive+no_connect"))
    )
    (net (code "336") (name "unconnected-(U2E-TEST_GPIO[46]_4-PadA3)") (class "Default")
      (node (ref "U2") (pin "A3") (pinfunction "TEST_GPIO[46]_4_A3") (pintype "passive+no_connect"))
    )
    (net (code "337") (name "unconnected-(U2E-TEST_GPIO[47]_4-PadD7)") (class "Default")
      (node (ref "U2") (pin "D7") (pinfunction "TEST_GPIO[47]_4_D7") (pintype "passive+no_connect"))
    )
    (net (code "338") (name "unconnected-(U2E-TEST_GPIO[48]_4-PadB5)") (class "Default")
      (node (ref "U2") (pin "B5") (pinfunction "TEST_GPIO[48]_4_B5") (pintype "passive+no_connect"))
    )
    (net (code "339") (name "unconnected-(U2E-TEST_GPIO[49]_4-PadA4)") (class "Default")
      (node (ref "U2") (pin "A4") (pinfunction "TEST_GPIO[49]_4_A4") (pintype "passive+no_connect"))
    )
    (net (code "340") (name "unconnected-(U2E-TEST_GPIO[50]_4-PadC7)") (class "Default")
      (node (ref "U2") (pin "C7") (pinfunction "TEST_GPIO[50]_4_C7") (pintype "passive+no_connect"))
    )
    (net (code "341") (name "unconnected-(U2E-TEST_GPIO[51]_4-PadB6)") (class "Default")
      (node (ref "U2") (pin "B6") (pinfunction "TEST_GPIO[51]_4_B6") (pintype "passive+no_connect"))
    )
    (net (code "342") (name "unconnected-(U2E-TEST_GPIO[52]_4-PadC13)") (class "Default")
      (node (ref "U2") (pin "C13") (pinfunction "TEST_GPIO[52]_4_C13") (pintype "passive+no_connect"))
    )
    (net (code "343") (name "unconnected-(U2E-TEST_GPIO[53]_4-PadB13)") (class "Default")
      (node (ref "U2") (pin "B13") (pinfunction "TEST_GPIO[53]_4_B13") (pintype "passive+no_connect"))
    )
    (net (code "344") (name "unconnected-(U2E-TEST_GPIO[54]_4-PadC14)") (class "Default")
      (node (ref "U2") (pin "C14") (pinfunction "TEST_GPIO[54]_4_C14") (pintype "passive+no_connect"))
    )
    (net (code "345") (name "unconnected-(U2E-TEST_GPIO[55]_4-PadD14)") (class "Default")
      (node (ref "U2") (pin "D14") (pinfunction "TEST_GPIO[55]_4_D14") (pintype "passive+no_connect"))
    )
    (net (code "346") (name "unconnected-(U2E-TEST_GPIO[56]_4-PadA13)") (class "Default")
      (node (ref "U2") (pin "A13") (pinfunction "TEST_GPIO[56]_4_A13") (pintype "passive+no_connect"))
    )
    (net (code "347") (name "unconnected-(U2E-TEST_GPIO[57]_4-PadA14)") (class "Default")
      (node (ref "U2") (pin "A14") (pinfunction "TEST_GPIO[57]_4_A14") (pintype "passive+no_connect"))
    )
    (net (code "348") (name "unconnected-(U2E-TEST_GPIO[58]_4-PadC15)") (class "Default")
      (node (ref "U2") (pin "C15") (pinfunction "TEST_GPIO[58]_4_C15") (pintype "passive+no_connect"))
    )
    (net (code "349") (name "unconnected-(U2E-TEST_GPIO[59]_4-PadD15)") (class "Default")
      (node (ref "U2") (pin "D15") (pinfunction "TEST_GPIO[59]_4_D15") (pintype "passive+no_connect"))
    )
    (net (code "350") (name "unconnected-(U2E-TEST_GPIO[60]_4-PadB15)") (class "Default")
      (node (ref "U2") (pin "B15") (pinfunction "TEST_GPIO[60]_4_B15") (pintype "passive+no_connect"))
    )
    (net (code "351") (name "unconnected-(U2E-TEST_GPIO[61]_4-PadA16)") (class "Default")
      (node (ref "U2") (pin "A16") (pinfunction "TEST_GPIO[61]_4_A16") (pintype "passive+no_connect"))
    )
    (net (code "352") (name "unconnected-(U2E-TEST_GPIO[62]_4-PadA15)") (class "Default")
      (node (ref "U2") (pin "A15") (pinfunction "TEST_GPIO[62]_4_A15") (pintype "passive+no_connect"))
    )
    (net (code "353") (name "unconnected-(U2E-TEST_GPIO[63]_4-PadB16)") (class "Default")
      (node (ref "U2") (pin "B16") (pinfunction "TEST_GPIO[63]_4_B16") (pintype "passive+no_connect"))
    )
    (net (code "354") (name "unconnected-(U2E-TEST_GPIO[64]_4-PadD16)") (class "Default")
      (node (ref "U2") (pin "D16") (pinfunction "TEST_GPIO[64]_4_D16") (pintype "passive+no_connect"))
    )
    (net (code "355") (name "unconnected-(U2E-TEST_GPIO[65]_4-PadC17)") (class "Default")
      (node (ref "U2") (pin "C17") (pinfunction "TEST_GPIO[65]_4_C17") (pintype "passive+no_connect"))
    )
    (net (code "356") (name "unconnected-(U2E-TEST_GPIO[66]_4-PadB17)") (class "Default")
      (node (ref "U2") (pin "B17") (pinfunction "TEST_GPIO[66]_4_B17") (pintype "passive+no_connect"))
    )
    (net (code "357") (name "unconnected-(U2E-TEST_GPIO[67]_4-PadD17)") (class "Default")
      (node (ref "U2") (pin "D17") (pinfunction "TEST_GPIO[67]_4_D17") (pintype "passive+no_connect"))
    )
    (net (code "358") (name "unconnected-(U2E-TEST_GPIO[68]_4-PadA18)") (class "Default")
      (node (ref "U2") (pin "A18") (pinfunction "TEST_GPIO[68]_4_A18") (pintype "passive+no_connect"))
    )
    (net (code "359") (name "unconnected-(U2E-TEST_GPIO[69]_4-PadC18)") (class "Default")
      (node (ref "U2") (pin "C18") (pinfunction "TEST_GPIO[69]_4_C18") (pintype "passive+no_connect"))
    )
    (net (code "360") (name "unconnected-(U2E-TEST_GPIO[70]_4-PadB18)") (class "Default")
      (node (ref "U2") (pin "B18") (pinfunction "TEST_GPIO[70]_4_B18") (pintype "passive+no_connect"))
    )
    (net (code "361") (name "unconnected-(U2E-TEST_GPIO[71]_4-PadE18)") (class "Default")
      (node (ref "U2") (pin "E18") (pinfunction "TEST_GPIO[71]_4_E18") (pintype "passive+no_connect"))
    )
  )
)
